# dc26-dev-boardv3.net
KiCad netlist of a schematic drawn in EAGLE
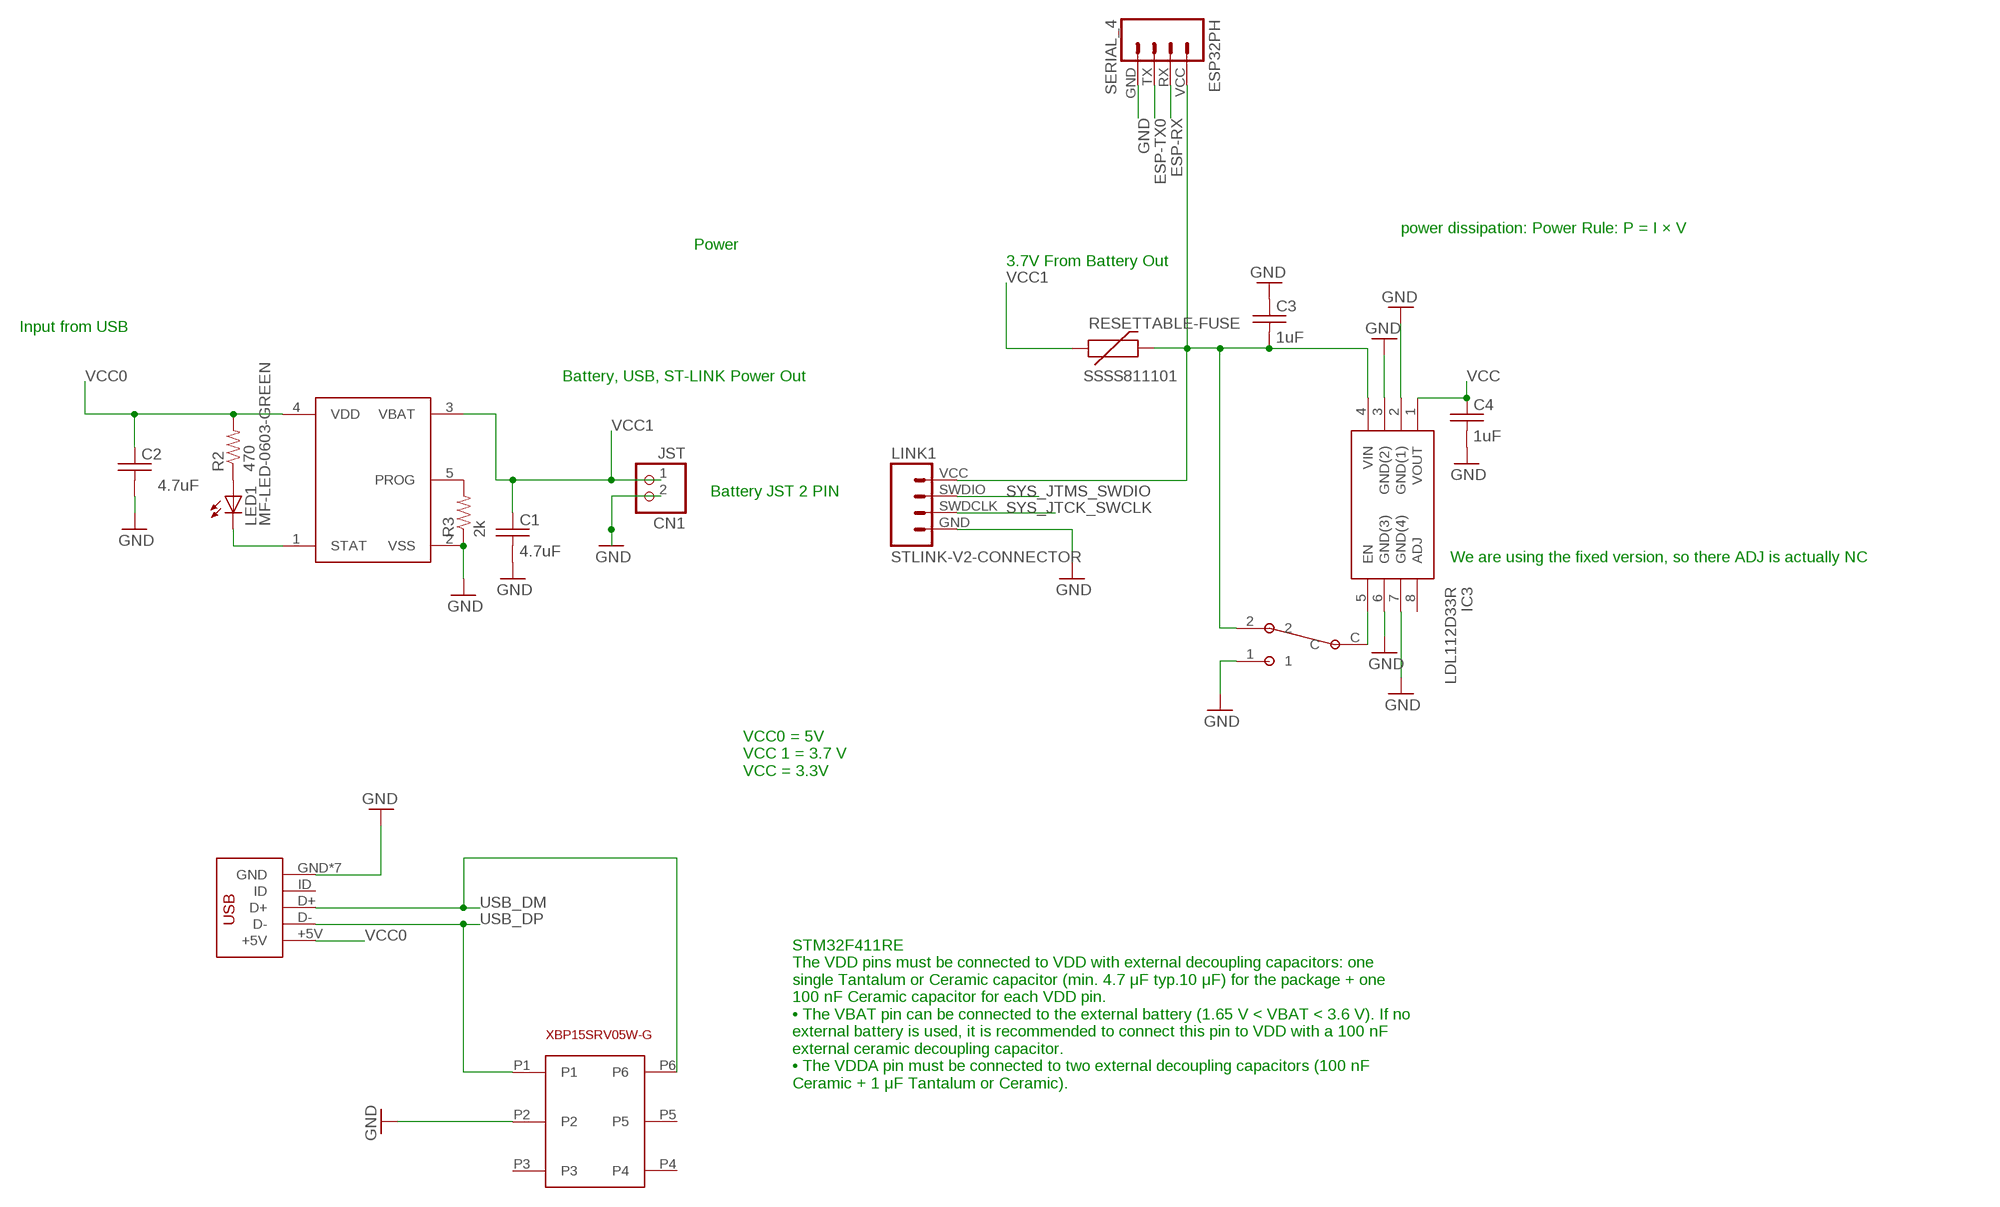
[diagram p0: schematic, sheet 1]
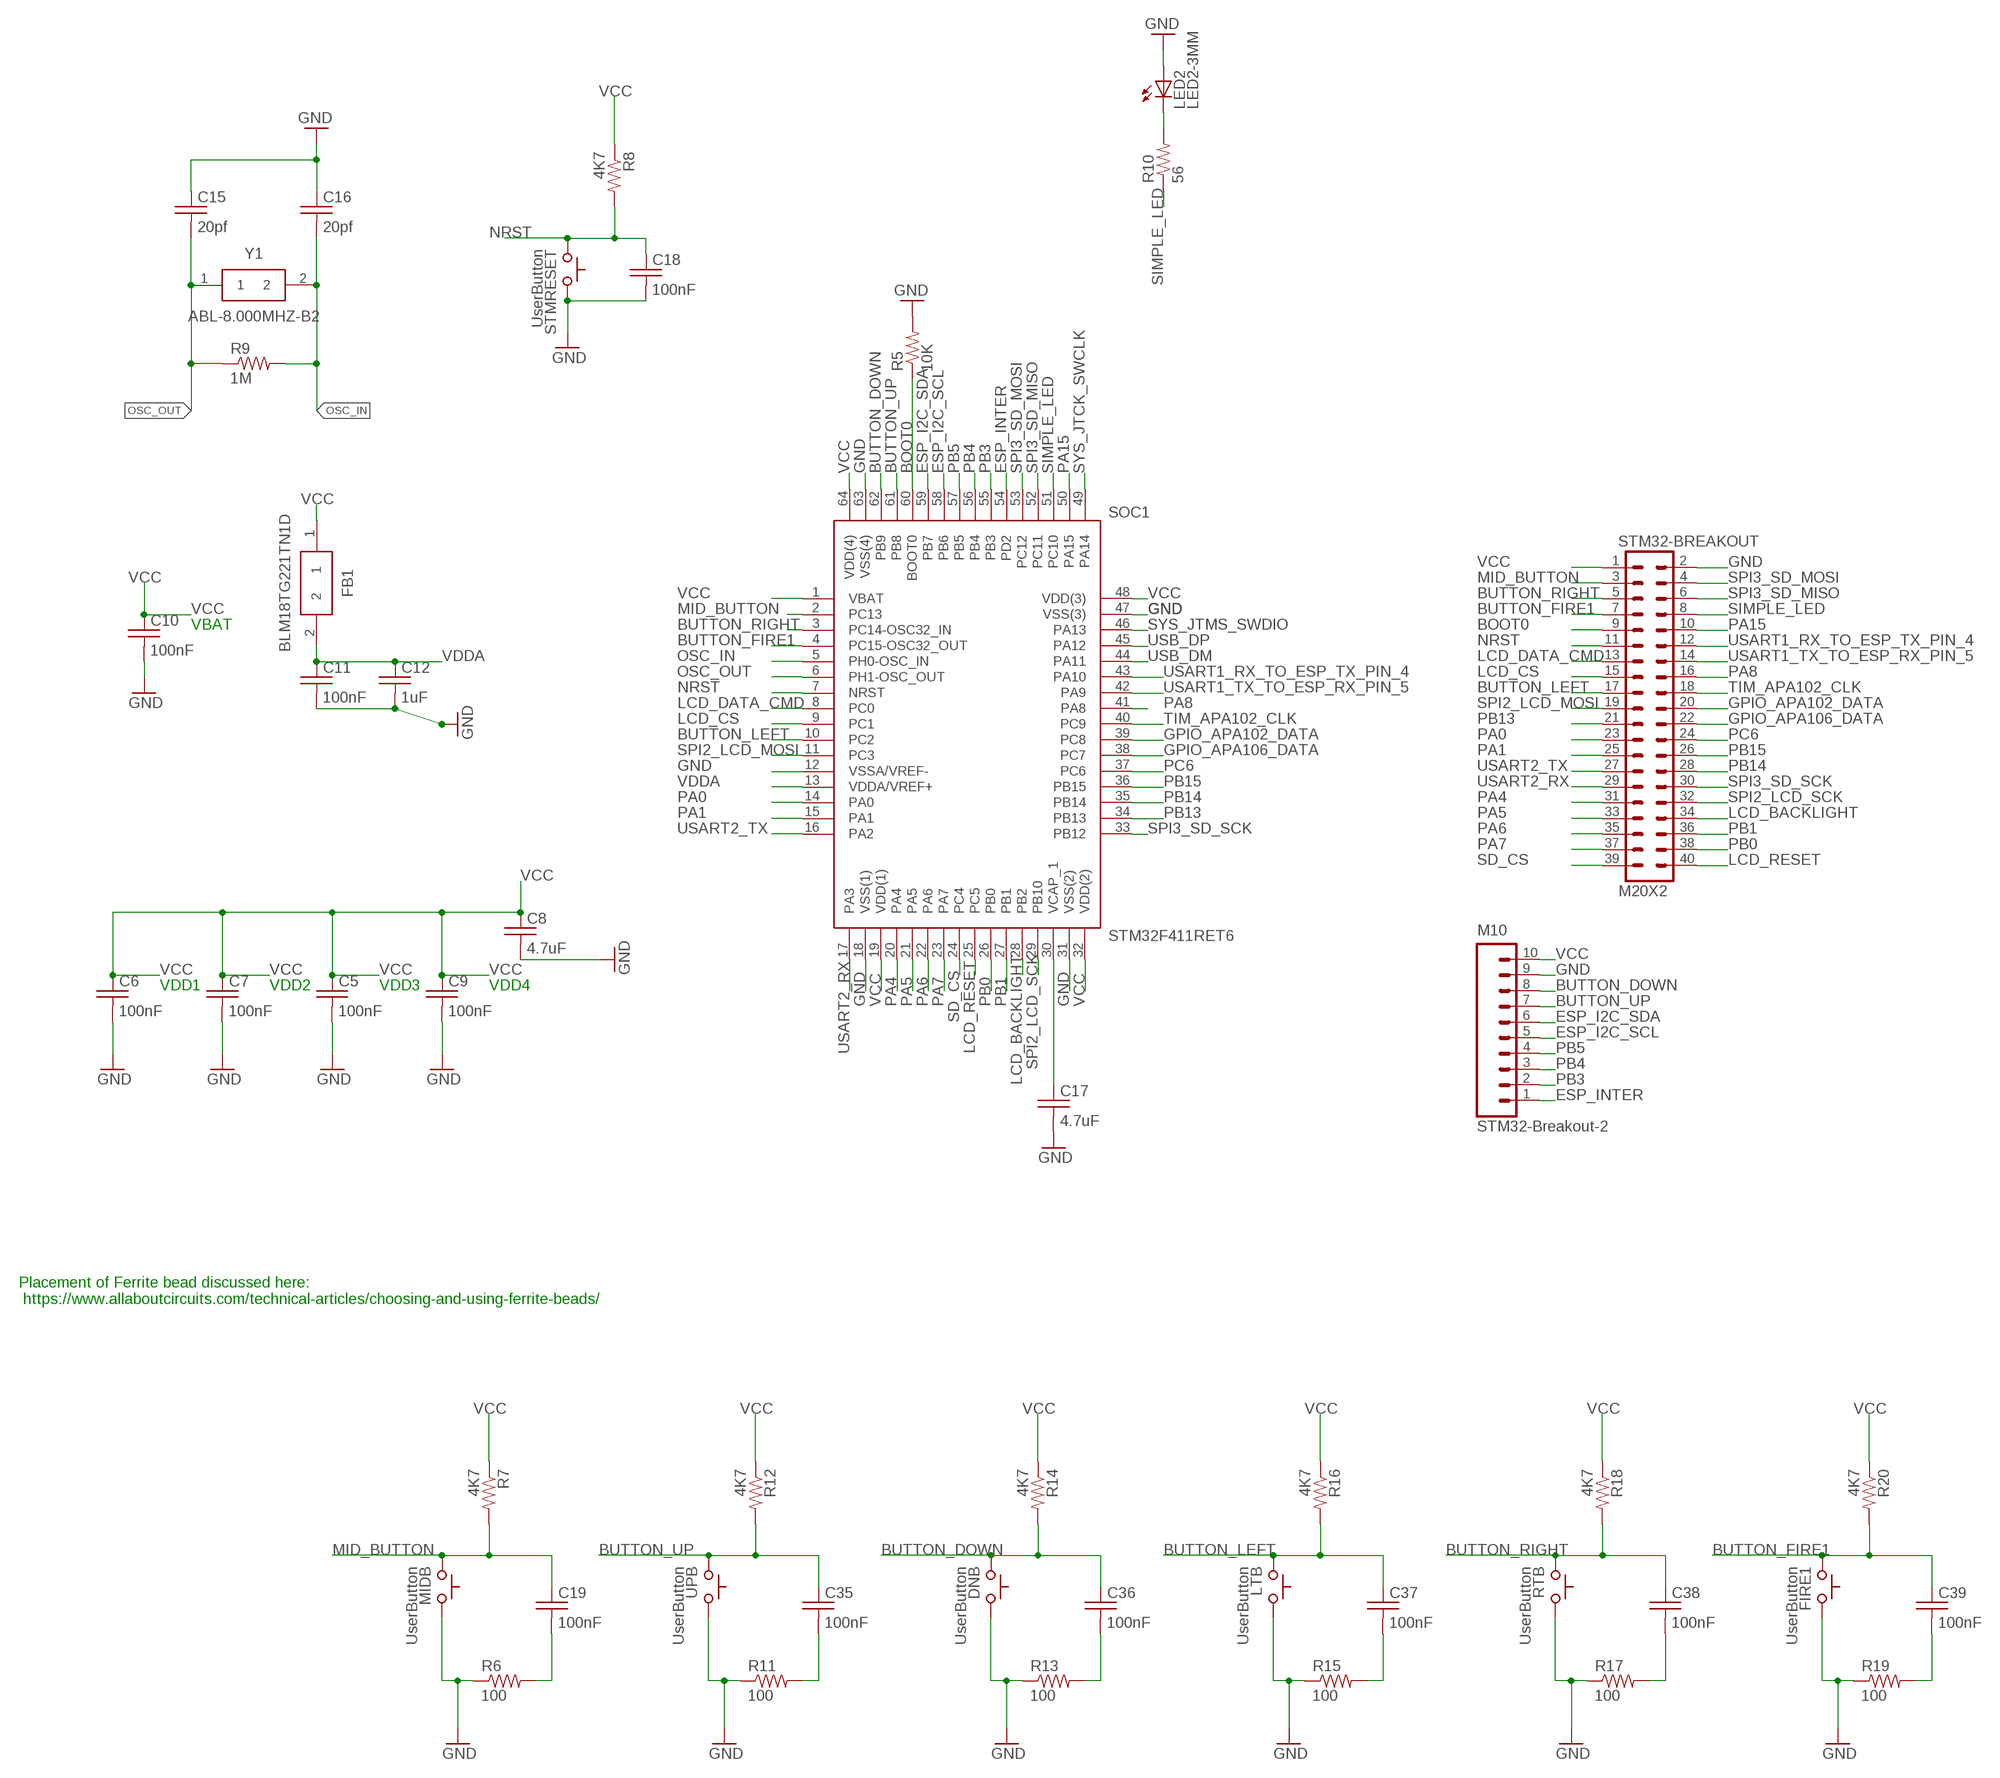
[diagram p1: schematic, sheet 2]
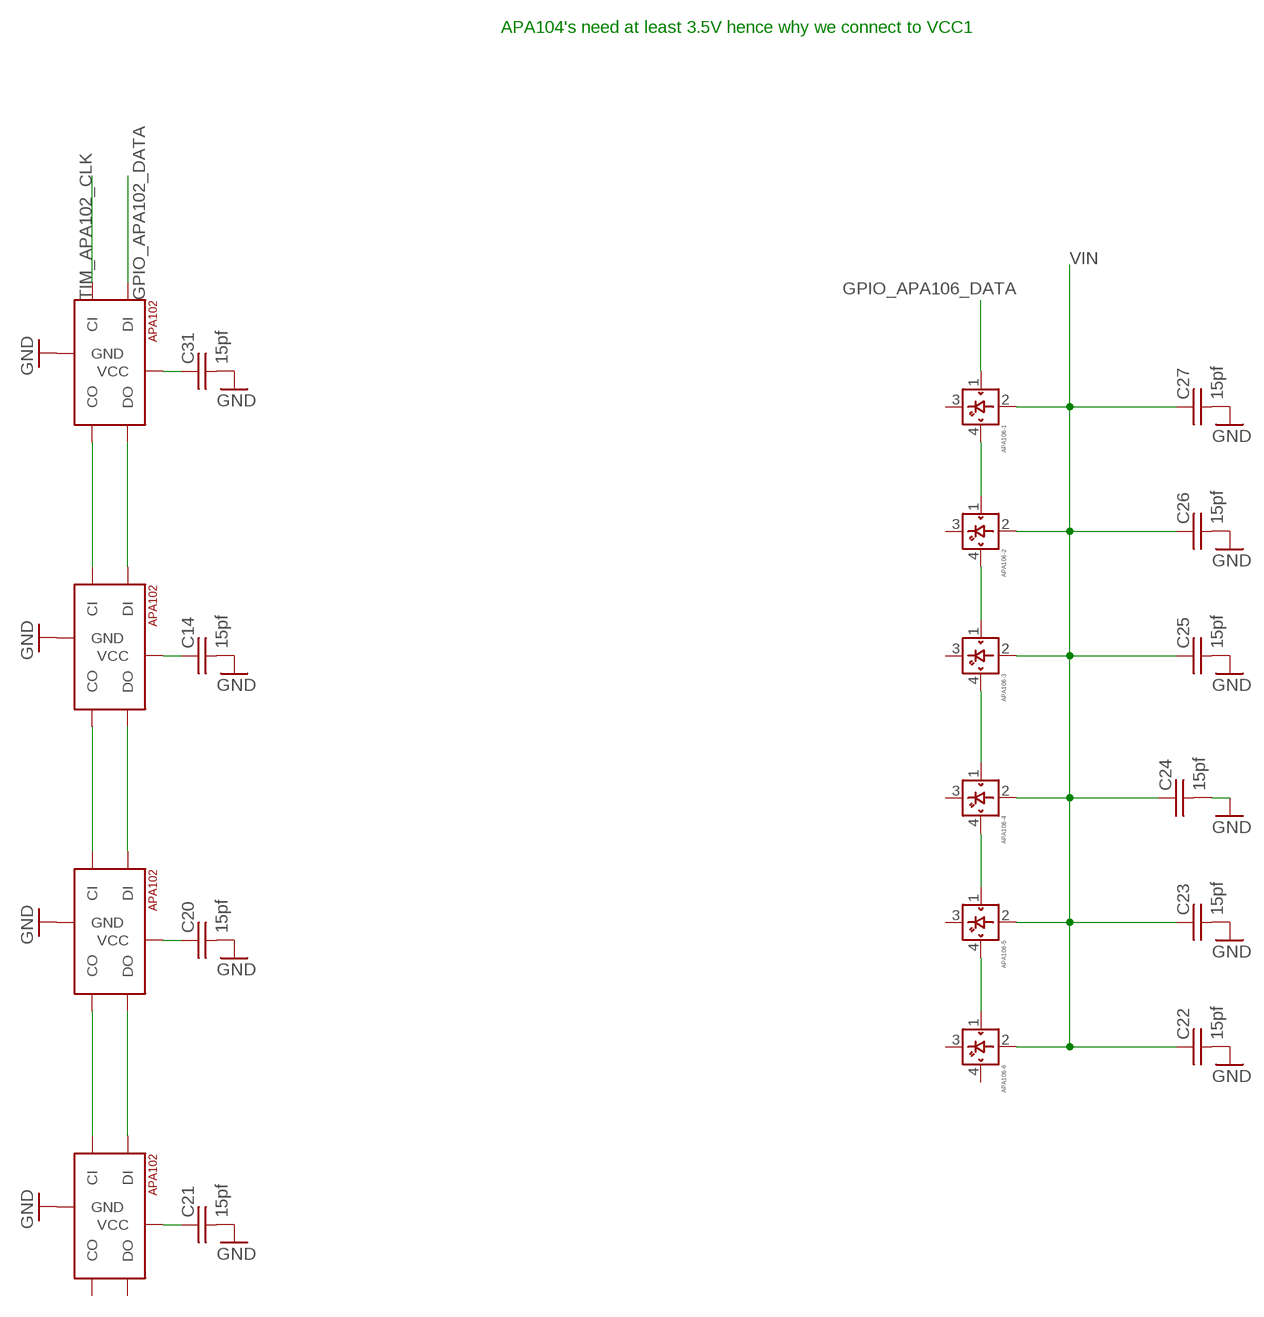
[diagram p2: schematic, sheet 3]
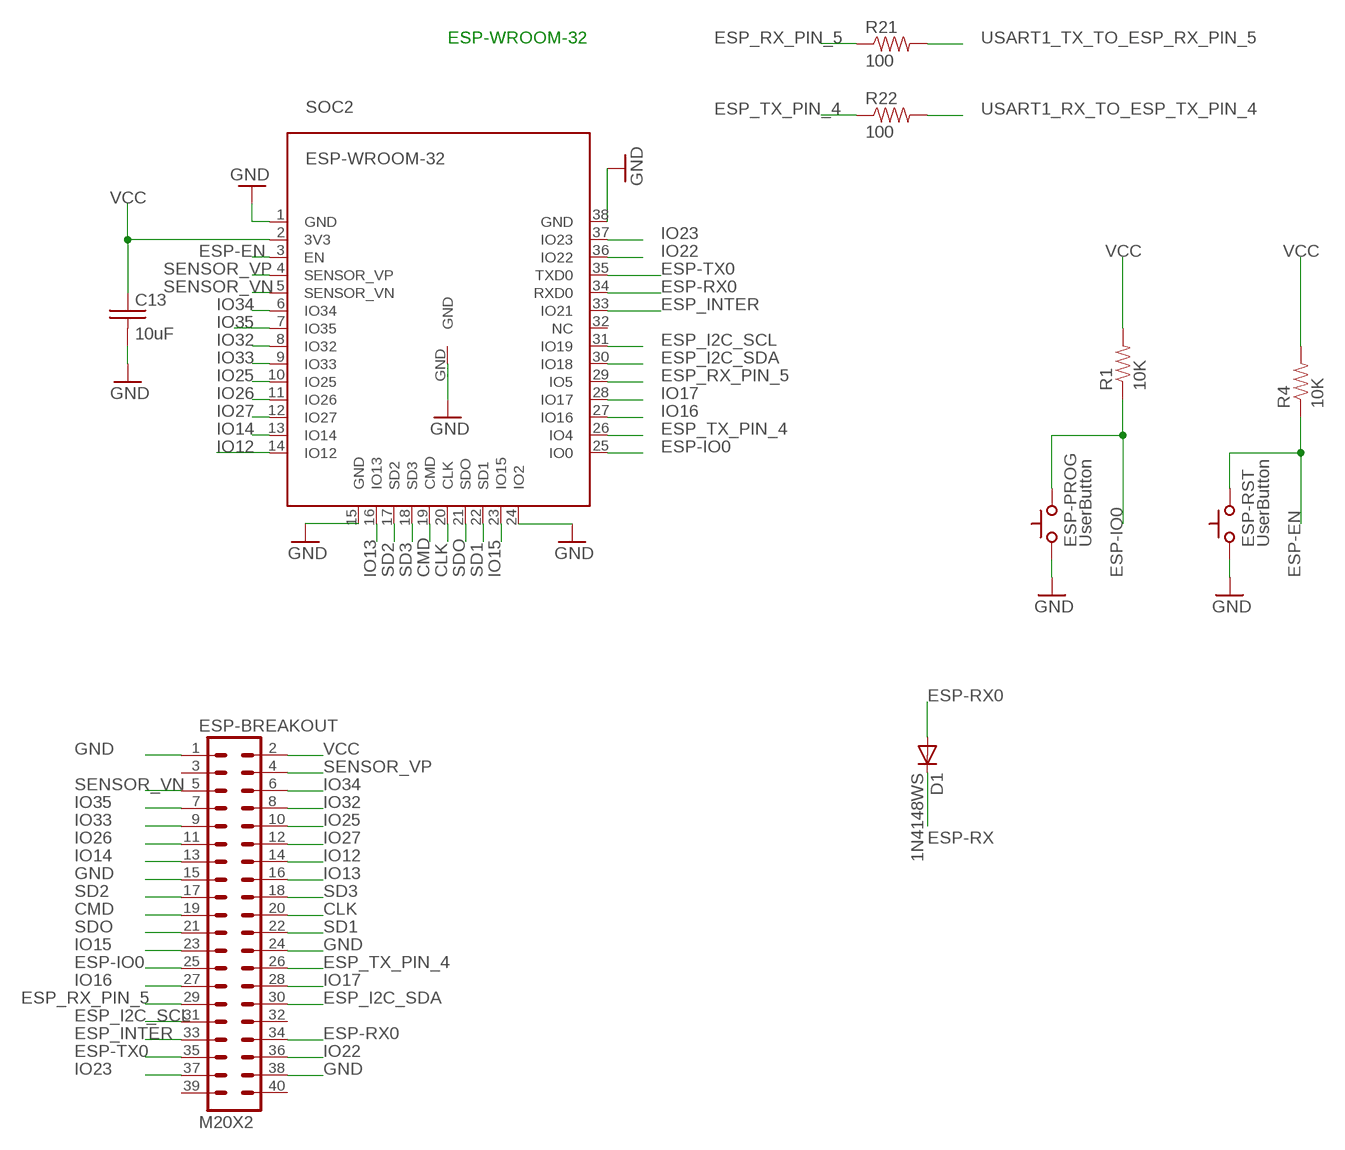
[diagram p3: schematic, sheet 4]
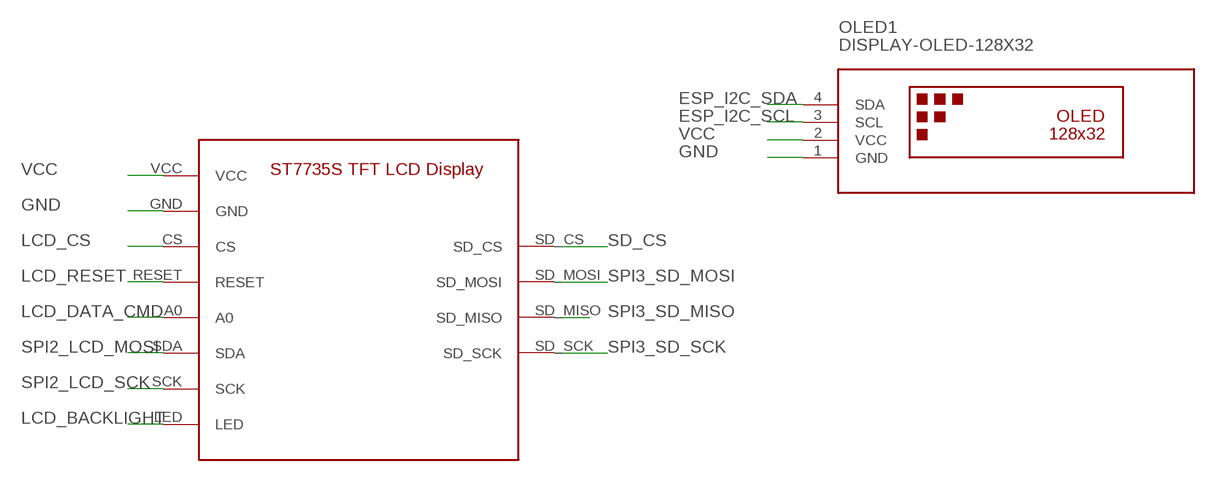
[diagram p4: schematic, sheet 5]
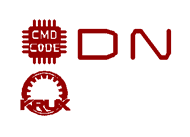
[diagram p5: schematic, sheet 6]
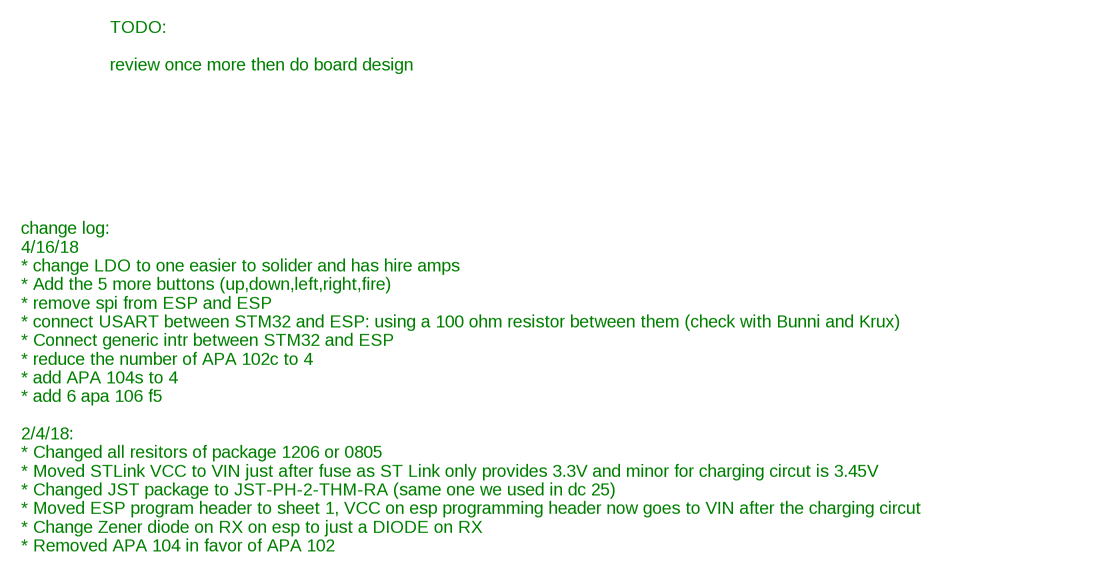
[diagram p6: schematic, sheet 7]

(export (version "E")
  (design (tool "Eeschema 10.0.6"))
  (components
    (comp (ref "C1")
      (value "4.7uF")
      (footprint "eagle-import:C0805")
      (libsource (lib "eagle-import") (part "C-USC0805"))
    )
    (comp (ref "C2")
      (value "4.7uF")
      (footprint "eagle-import:C0805")
      (libsource (lib "eagle-import") (part "C-USC0805"))
    )
    (comp (ref "C3")
      (value "1uF")
      (footprint "eagle-import:C0805")
      (libsource (lib "eagle-import") (part "C-USC0805"))
    )
    (comp (ref "C4")
      (value "1uF")
      (footprint "eagle-import:C0805")
      (libsource (lib "eagle-import") (part "C-USC0805"))
    )
    (comp (ref "CHARGING_CIRCUT")
      (value "MCP73831")
      (footprint "eagle-import:SOT23-5")
      (libsource (lib "eagle-import") (part "DS21984E"))
    )
    (comp (ref "CN1")
      (value "JST")
      (footprint "eagle-import:JST-PH-2-THM-RA")
      (libsource (lib "eagle-import") (part "JST_2PIN-THM-RA"))
    )
    (comp (ref "ESP32PH")
      (value "SERIAL_4")
      (footprint "eagle-import:SERIAL_HEADER_4")
      (libsource (lib "eagle-import") (part "SERIAL_4"))
    )
    (comp (ref "IC3")
      (value "LDL112D33R")
      (footprint "eagle-import:SOIC127P600X175-8N")
      (libsource (lib "eagle-import") (part "LDL112D33R"))
    )
    (comp (ref "LED1")
      (value "MF-LED-0603-GREEN")
      (footprint "eagle-import:LED-1206")
      (libsource (lib "eagle-import") (part "LED1206"))
    )
    (comp (ref "LINK1")
      (value "STLINK-V2-CONNECTOR")
      (footprint "eagle-import:1X04")
      (libsource (lib "eagle-import") (part "STLINK-V2-CONNECTOR"))
    )
    (comp (ref "P1")
      (value "SSSS811101")
      (footprint "eagle-import:SPDT_SSAJ120100")
      (libsource (lib "eagle-import") (part "SWITCH_SPDT"))
    )
    (comp (ref "R2")
      (value "470")
      (footprint "eagle-import:0805")
      (libsource (lib "eagle-import") (part "RESISTOR0805-RES"))
    )
    (comp (ref "R3")
      (value "2k")
      (footprint "eagle-import:0805")
      (libsource (lib "eagle-import") (part "RESISTOR0805-RES"))
    )
    (comp (ref "RESETTABLE-FUSE")
      (value "SSSS811101")
      (footprint "eagle-import:PTC-1206")
      (libsource (lib "eagle-import") (part "PTCSMD"))
    )
    (comp (ref "U$17")
      (value "XBP15SRV05W-G")
      (footprint "eagle-import:SOT-26P-XBP15SRV05W-G")
      (fields (field (name "DIGI_KEY_PART_NUMBER") "893-1422-1-ND"))
      (libsource (lib "eagle-import") (part "XBP15SRV05W-G"))
    )
    (comp (ref "USB")
      (value "DX4R005JJ2DX4R005JJ2")
      (footprint "eagle-import:DX4R005JJ2")
      (libsource (lib "eagle-import") (part "DX4R005JJ2DX4R005JJ2"))
    )
    (comp (ref "LCD1")
      (value "ST7735S_LCD_MODULE")
      (footprint "eagle-import:ST7735S_LCD_DISPLAY")
      (libsource (lib "eagle-import") (part "ST7735S_LCD_MODULE"))
    )
    (comp (ref "OLED1")
      (value "DISPLAY-OLED-128X32")
      (footprint "eagle-import:DISPLAY-OLED-128X32")
      (libsource (lib "eagle-import") (part "DISPLAY-OLED-128X32"))
    )
    (comp (ref "C13")
      (value "10uF")
      (footprint "eagle-import:C0805")
      (libsource (lib "eagle-import") (part "C-USC0805"))
    )
    (comp (ref "D1")
      (value "1N4148WS")
      (footprint "eagle-import:SOD-323")
      (libsource (lib "eagle-import") (part "DIODESOD"))
    )
    (comp (ref "ESP-BREAKOUT")
      (value "M20X2")
      (footprint "eagle-import:2X20")
      (libsource (lib "eagle-import") (part "M20X2"))
    )
    (comp (ref "ESP-PROG")
      (value "UserButton")
      (footprint "eagle-import:TACTILE-2PIN-NARROW")
      (libsource (lib "eagle-import") (part "SWITCH_TACTILETACTILE-2PIN-NARROW"))
    )
    (comp (ref "ESP-RST")
      (value "UserButton")
      (footprint "eagle-import:TACTILE-2PIN-NARROW")
      (libsource (lib "eagle-import") (part "SWITCH_TACTILETACTILE-2PIN-NARROW"))
    )
    (comp (ref "R1")
      (value "10K")
      (footprint "eagle-import:0805")
      (libsource (lib "eagle-import") (part "RESISTOR0805-RES"))
    )
    (comp (ref "R4")
      (value "10K")
      (footprint "eagle-import:0805")
      (libsource (lib "eagle-import") (part "RESISTOR0805-RES"))
    )
    (comp (ref "R21")
      (value "100")
      (footprint "eagle-import:0805")
      (libsource (lib "eagle-import") (part "RESISTOR0805-RES"))
    )
    (comp (ref "R22")
      (value "100")
      (footprint "eagle-import:0805")
      (libsource (lib "eagle-import") (part "RESISTOR0805-RES"))
    )
    (comp (ref "SOC2")
      (value "ESP-WROOM-32")
      (footprint "eagle-import:ESP-WROOM-32")
      (libsource (lib "eagle-import") (part "ESP-WROOM-32"))
    )
    (comp (ref "APA102-1")
      (value "APA1025050")
      (footprint "eagle-import:APA102_5050")
      (libsource (lib "eagle-import") (part "APA1025050"))
    )
    (comp (ref "APA102-2")
      (value "APA1025050")
      (footprint "eagle-import:APA102_5050")
      (libsource (lib "eagle-import") (part "APA1025050"))
    )
    (comp (ref "APA102-3")
      (value "APA1025050")
      (footprint "eagle-import:APA102_5050")
      (libsource (lib "eagle-import") (part "APA1025050"))
    )
    (comp (ref "APA102-4")
      (value "APA1025050")
      (footprint "eagle-import:APA102_5050")
      (libsource (lib "eagle-import") (part "APA1025050"))
    )
    (comp (ref "APA106-1")
      (value "APA-106")
      (footprint "eagle-import:WS2812F5_STRAIGHT")
      (libsource (lib "eagle-import") (part "APA-106"))
    )
    (comp (ref "APA106-2")
      (value "APA-106")
      (footprint "eagle-import:WS2812F5_STRAIGHT")
      (libsource (lib "eagle-import") (part "APA-106"))
    )
    (comp (ref "APA106-3")
      (value "APA-106")
      (footprint "eagle-import:WS2812F5_STRAIGHT")
      (libsource (lib "eagle-import") (part "APA-106"))
    )
    (comp (ref "APA106-4")
      (value "APA-106")
      (footprint "eagle-import:WS2812F5_STRAIGHT")
      (libsource (lib "eagle-import") (part "APA-106"))
    )
    (comp (ref "APA106-5")
      (value "APA-106")
      (footprint "eagle-import:WS2812F5_STRAIGHT")
      (libsource (lib "eagle-import") (part "APA-106"))
    )
    (comp (ref "APA106-6")
      (value "APA-106")
      (footprint "eagle-import:WS2812F5_STRAIGHT")
      (libsource (lib "eagle-import") (part "APA-106"))
    )
    (comp (ref "C14")
      (value "15pf")
      (footprint "eagle-import:C0805")
      (libsource (lib "eagle-import") (part "C-USC0805"))
    )
    (comp (ref "C20")
      (value "15pf")
      (footprint "eagle-import:C0805")
      (libsource (lib "eagle-import") (part "C-USC0805"))
    )
    (comp (ref "C21")
      (value "15pf")
      (footprint "eagle-import:C0805")
      (libsource (lib "eagle-import") (part "C-USC0805"))
    )
    (comp (ref "C22")
      (value "15pf")
      (footprint "eagle-import:C0805")
      (libsource (lib "eagle-import") (part "C-USC0805"))
    )
    (comp (ref "C23")
      (value "15pf")
      (footprint "eagle-import:C0805")
      (libsource (lib "eagle-import") (part "C-USC0805"))
    )
    (comp (ref "C24")
      (value "15pf")
      (footprint "eagle-import:C0805")
      (libsource (lib "eagle-import") (part "C-USC0805"))
    )
    (comp (ref "C25")
      (value "15pf")
      (footprint "eagle-import:C0805")
      (libsource (lib "eagle-import") (part "C-USC0805"))
    )
    (comp (ref "C26")
      (value "15pf")
      (footprint "eagle-import:C0805")
      (libsource (lib "eagle-import") (part "C-USC0805"))
    )
    (comp (ref "C27")
      (value "15pf")
      (footprint "eagle-import:C0805")
      (libsource (lib "eagle-import") (part "C-USC0805"))
    )
    (comp (ref "C31")
      (value "15pf")
      (footprint "eagle-import:C0805")
      (libsource (lib "eagle-import") (part "C-USC0805"))
    )
    (comp (ref "U$2")
      (value "CMD_C0DE_LOGO")
      (footprint "eagle-import:CMD_C0DE_LOGO")
      (libsource (lib "eagle-import") (part "CMD_C0DE_LOGO"))
    )
    (comp (ref "U$3")
      (value "DARKNET_DD")
      (footprint "eagle-import:DARKNET_D")
      (libsource (lib "eagle-import") (part "DARKNET_DD"))
    )
    (comp (ref "U$4")
      (value "DARKNET_NN")
      (footprint "eagle-import:DARKNET_N")
      (libsource (lib "eagle-import") (part "DARKNET_NN"))
    )
    (comp (ref "U$16")
      (value "KRUX_LOGO")
      (footprint "eagle-import:KRUX_LOGO")
      (libsource (lib "eagle-import") (part "KRUX_LOGO"))
    )
    (comp (ref "C5")
      (value "100nF")
      (footprint "eagle-import:C0805")
      (libsource (lib "eagle-import") (part "C-USC0805"))
    )
    (comp (ref "C6")
      (value "100nF")
      (footprint "eagle-import:C0805")
      (libsource (lib "eagle-import") (part "C-USC0805"))
    )
    (comp (ref "C7")
      (value "100nF")
      (footprint "eagle-import:C0805")
      (libsource (lib "eagle-import") (part "C-USC0805"))
    )
    (comp (ref "C8")
      (value "4.7uF")
      (footprint "eagle-import:C0805")
      (libsource (lib "eagle-import") (part "C-USC0805"))
    )
    (comp (ref "C9")
      (value "100nF")
      (footprint "eagle-import:C0805")
      (libsource (lib "eagle-import") (part "C-USC0805"))
    )
    (comp (ref "C10")
      (value "100nF")
      (footprint "eagle-import:C0805")
      (libsource (lib "eagle-import") (part "C-USC0805"))
    )
    (comp (ref "C11")
      (value "100nF")
      (footprint "eagle-import:C0805")
      (libsource (lib "eagle-import") (part "C-USC0805"))
    )
    (comp (ref "C12")
      (value "1uF")
      (footprint "eagle-import:C0805")
      (libsource (lib "eagle-import") (part "C-USC0805"))
    )
    (comp (ref "C15")
      (value "20pf")
      (footprint "eagle-import:C0805")
      (libsource (lib "eagle-import") (part "C-USC0805"))
    )
    (comp (ref "C16")
      (value "20pf")
      (footprint "eagle-import:C0805")
      (libsource (lib "eagle-import") (part "C-USC0805"))
    )
    (comp (ref "C17")
      (value "4.7uF")
      (footprint "eagle-import:C0805")
      (libsource (lib "eagle-import") (part "C-USC0805"))
    )
    (comp (ref "C18")
      (value "100nF")
      (footprint "eagle-import:C0805")
      (libsource (lib "eagle-import") (part "C-USC0805"))
    )
    (comp (ref "C19")
      (value "100nF")
      (footprint "eagle-import:C0805")
      (libsource (lib "eagle-import") (part "C-USC0805"))
    )
    (comp (ref "C35")
      (value "100nF")
      (footprint "eagle-import:C0805")
      (libsource (lib "eagle-import") (part "C-USC0805"))
    )
    (comp (ref "C36")
      (value "100nF")
      (footprint "eagle-import:C0805")
      (libsource (lib "eagle-import") (part "C-USC0805"))
    )
    (comp (ref "C37")
      (value "100nF")
      (footprint "eagle-import:C0805")
      (libsource (lib "eagle-import") (part "C-USC0805"))
    )
    (comp (ref "C38")
      (value "100nF")
      (footprint "eagle-import:C0805")
      (libsource (lib "eagle-import") (part "C-USC0805"))
    )
    (comp (ref "C39")
      (value "100nF")
      (footprint "eagle-import:C0805")
      (libsource (lib "eagle-import") (part "C-USC0805"))
    )
    (comp (ref "DNB")
      (value "UserButton")
      (footprint "eagle-import:TACTILE-2PIN-NARROW")
      (libsource (lib "eagle-import") (part "SWITCH_TACTILETACTILE-2PIN-NARROW"))
    )
    (comp (ref "FB1")
      (value "BLM18TG221TN1D")
      (footprint "eagle-import:BEADC1608X75N")
      (fields (field (name "RS_PART_NUMBER") "6197526"))
      (libsource (lib "eagle-import") (part "BLM18TG221TN1D"))
    )
    (comp (ref "FIRE1")
      (value "UserButton")
      (footprint "eagle-import:TACTILE-2PIN-NARROW")
      (libsource (lib "eagle-import") (part "SWITCH_TACTILETACTILE-2PIN-NARROW"))
    )
    (comp (ref "LED2")
      (value "LED2-3MM")
      (footprint "eagle-import:LED3MM")
      (libsource (lib "eagle-import") (part "LED3MM"))
    )
    (comp (ref "LTB")
      (value "UserButton")
      (footprint "eagle-import:TACTILE-2PIN-NARROW")
      (libsource (lib "eagle-import") (part "SWITCH_TACTILETACTILE-2PIN-NARROW"))
    )
    (comp (ref "M10")
      (value "STM32-Breakout-2")
      (footprint "eagle-import:1X10")
      (libsource (lib "eagle-import") (part "M10SILK_FEMALE_PTH"))
    )
    (comp (ref "MIDB")
      (value "UserButton")
      (footprint "eagle-import:TACTILE-2PIN-NARROW")
      (libsource (lib "eagle-import") (part "SWITCH_TACTILETACTILE-2PIN-NARROW"))
    )
    (comp (ref "R5")
      (value "10K")
      (footprint "eagle-import:0805")
      (libsource (lib "eagle-import") (part "RESISTOR0805-RES"))
    )
    (comp (ref "R6")
      (value "100")
      (footprint "eagle-import:0805")
      (libsource (lib "eagle-import") (part "RESISTOR0805-RES"))
    )
    (comp (ref "R7")
      (value "4K7")
      (footprint "eagle-import:0805")
      (libsource (lib "eagle-import") (part "RESISTOR0805-RES"))
    )
    (comp (ref "R8")
      (value "4K7")
      (footprint "eagle-import:0805")
      (libsource (lib "eagle-import") (part "RESISTOR0805-RES"))
    )
    (comp (ref "R9")
      (value "1M")
      (footprint "eagle-import:0805")
      (libsource (lib "eagle-import") (part "RESISTOR0805-RES"))
    )
    (comp (ref "R10")
      (value "56")
      (footprint "eagle-import:0805")
      (libsource (lib "eagle-import") (part "RESISTOR0805-RES"))
    )
    (comp (ref "R11")
      (value "100")
      (footprint "eagle-import:0805")
      (libsource (lib "eagle-import") (part "RESISTOR0805-RES"))
    )
    (comp (ref "R12")
      (value "4K7")
      (footprint "eagle-import:0805")
      (libsource (lib "eagle-import") (part "RESISTOR0805-RES"))
    )
    (comp (ref "R13")
      (value "100")
      (footprint "eagle-import:0805")
      (libsource (lib "eagle-import") (part "RESISTOR0805-RES"))
    )
    (comp (ref "R14")
      (value "4K7")
      (footprint "eagle-import:0805")
      (libsource (lib "eagle-import") (part "RESISTOR0805-RES"))
    )
    (comp (ref "R15")
      (value "100")
      (footprint "eagle-import:0805")
      (libsource (lib "eagle-import") (part "RESISTOR0805-RES"))
    )
    (comp (ref "R16")
      (value "4K7")
      (footprint "eagle-import:0805")
      (libsource (lib "eagle-import") (part "RESISTOR0805-RES"))
    )
    (comp (ref "R17")
      (value "100")
      (footprint "eagle-import:0805")
      (libsource (lib "eagle-import") (part "RESISTOR0805-RES"))
    )
    (comp (ref "R18")
      (value "4K7")
      (footprint "eagle-import:0805")
      (libsource (lib "eagle-import") (part "RESISTOR0805-RES"))
    )
    (comp (ref "R19")
      (value "100")
      (footprint "eagle-import:0805")
      (libsource (lib "eagle-import") (part "RESISTOR0805-RES"))
    )
    (comp (ref "R20")
      (value "4K7")
      (footprint "eagle-import:0805")
      (libsource (lib "eagle-import") (part "RESISTOR0805-RES"))
    )
    (comp (ref "RTB")
      (value "UserButton")
      (footprint "eagle-import:TACTILE-2PIN-NARROW")
      (libsource (lib "eagle-import") (part "SWITCH_TACTILETACTILE-2PIN-NARROW"))
    )
    (comp (ref "SOC1")
      (value "STM32F411RET6")
      (footprint "eagle-import:QFP50P1200X1200X160-64N")
      (fields (field (name "RS_PART_NUMBER") "1106617P"))
      (libsource (lib "eagle-import") (part "STM32F411RET6"))
    )
    (comp (ref "STM32-BREAKOUT")
      (value "M20X2")
      (footprint "eagle-import:2X20")
      (libsource (lib "eagle-import") (part "M20X2"))
    )
    (comp (ref "STMRESET")
      (value "UserButton")
      (footprint "eagle-import:TACTILE-2PIN-NARROW")
      (libsource (lib "eagle-import") (part "SWITCH_TACTILETACTILE-2PIN-NARROW"))
    )
    (comp (ref "UPB")
      (value "UserButton")
      (footprint "eagle-import:TACTILE-2PIN-NARROW")
      (libsource (lib "eagle-import") (part "SWITCH_TACTILETACTILE-2PIN-NARROW"))
    )
    (comp (ref "Y1")
      (value "ABL-8.000MHZ-B2")
      (footprint "eagle-import:HC_49US_(AT49)PTH")
      (libsource (lib "eagle-import") (part "ABL-8.000MHZ-B2"))
    )
  )
  (nets
    (net (code "1") (name "BOOT0") (class "Default")
      (node (ref "R5") (pin "1") (pinfunction "1_1") (pintype "passive"))
      (node (ref "SOC1") (pin "60") (pinfunction "BOOT0_60") (pintype "passive"))
      (node (ref "STM32-BREAKOUT") (pin "9") (pinfunction "9_9") (pintype "passive"))
    )
    (net (code "2") (name "BUTTON_DOWN") (class "Default")
      (node (ref "C36") (pin "1") (pinfunction "1_1") (pintype "passive"))
      (node (ref "DNB") (pin "P$2") (pinfunction "C_P$2") (pintype "passive"))
      (node (ref "M10") (pin "8") (pinfunction "8_8") (pintype "passive"))
      (node (ref "R14") (pin "2") (pinfunction "2_2") (pintype "passive"))
      (node (ref "SOC1") (pin "62") (pinfunction "PB9_62") (pintype "passive"))
    )
    (net (code "3") (name "BUTTON_FIRE1") (class "Default")
      (node (ref "C39") (pin "1") (pinfunction "1_1") (pintype "passive"))
      (node (ref "FIRE1") (pin "P$2") (pinfunction "C_P$2") (pintype "passive"))
      (node (ref "R20") (pin "2") (pinfunction "2_2") (pintype "passive"))
      (node (ref "SOC1") (pin "4") (pinfunction "PC15-OSC32_OUT_4") (pintype "passive"))
      (node (ref "STM32-BREAKOUT") (pin "7") (pinfunction "7_7") (pintype "passive"))
    )
    (net (code "4") (name "BUTTON_LEFT") (class "Default")
      (node (ref "C37") (pin "1") (pinfunction "1_1") (pintype "passive"))
      (node (ref "LTB") (pin "P$2") (pinfunction "C_P$2") (pintype "passive"))
      (node (ref "R16") (pin "2") (pinfunction "2_2") (pintype "passive"))
      (node (ref "SOC1") (pin "10") (pinfunction "PC2_10") (pintype "passive"))
      (node (ref "STM32-BREAKOUT") (pin "17") (pinfunction "17_17") (pintype "passive"))
    )
    (net (code "5") (name "BUTTON_RIGHT") (class "Default")
      (node (ref "C38") (pin "1") (pinfunction "1_1") (pintype "passive"))
      (node (ref "R18") (pin "2") (pinfunction "2_2") (pintype "passive"))
      (node (ref "RTB") (pin "P$2") (pinfunction "C_P$2") (pintype "passive"))
      (node (ref "SOC1") (pin "3") (pinfunction "PC14-OSC32_IN_3") (pintype "passive"))
      (node (ref "STM32-BREAKOUT") (pin "5") (pinfunction "5_5") (pintype "passive"))
    )
    (net (code "6") (name "BUTTON_UP") (class "Default")
      (node (ref "C35") (pin "1") (pinfunction "1_1") (pintype "passive"))
      (node (ref "M10") (pin "7") (pinfunction "7_7") (pintype "passive"))
      (node (ref "R12") (pin "2") (pinfunction "2_2") (pintype "passive"))
      (node (ref "SOC1") (pin "61") (pinfunction "PB8_61") (pintype "passive"))
      (node (ref "UPB") (pin "P$2") (pinfunction "C_P$2") (pintype "passive"))
    )
    (net (code "7") (name "CLK") (class "Default")
      (node (ref "ESP-BREAKOUT") (pin "20") (pinfunction "20_20") (pintype "passive"))
      (node (ref "SOC2") (pin "20") (pinfunction "CLK_20") (pintype "bidirectional"))
    )
    (net (code "8") (name "CMD") (class "Default")
      (node (ref "ESP-BREAKOUT") (pin "19") (pinfunction "19_19") (pintype "passive"))
      (node (ref "SOC2") (pin "19") (pinfunction "CMD_19") (pintype "bidirectional"))
    )
    (net (code "9") (name "ESP-EN") (class "Default")
      (node (ref "ESP-RST") (pin "P$1") (pinfunction "A_P$1") (pintype "passive"))
      (node (ref "R4") (pin "1") (pinfunction "1_1") (pintype "passive"))
      (node (ref "SOC2") (pin "3") (pinfunction "EN_3") (pintype "bidirectional"))
    )
    (net (code "10") (name "ESP-IO0") (class "Default")
      (node (ref "ESP-BREAKOUT") (pin "25") (pinfunction "25_25") (pintype "passive"))
      (node (ref "ESP-PROG") (pin "P$1") (pinfunction "A_P$1") (pintype "passive"))
      (node (ref "R1") (pin "1") (pinfunction "1_1") (pintype "passive"))
      (node (ref "SOC2") (pin "25") (pinfunction "IO0_25") (pintype "bidirectional"))
    )
    (net (code "11") (name "ESP-RX") (class "Default")
      (node (ref "D1") (pin "1") (pinfunction "C_1") (pintype "passive"))
      (node (ref "ESP32PH") (pin "RX") (pinfunction "RX_RX") (pintype "bidirectional"))
    )
    (net (code "12") (name "ESP-RX0") (class "Default")
      (node (ref "D1") (pin "2") (pinfunction "A_2") (pintype "passive"))
      (node (ref "ESP-BREAKOUT") (pin "34") (pinfunction "34_34") (pintype "passive"))
      (node (ref "SOC2") (pin "34") (pinfunction "RXD0_34") (pintype "bidirectional"))
    )
    (net (code "13") (name "ESP-TX0") (class "Default")
      (node (ref "ESP-BREAKOUT") (pin "35") (pinfunction "35_35") (pintype "passive"))
      (node (ref "ESP32PH") (pin "TX") (pinfunction "TX_TX") (pintype "input"))
      (node (ref "SOC2") (pin "35") (pinfunction "TXD0_35") (pintype "bidirectional"))
    )
    (net (code "14") (name "ESP_I2C_SCL") (class "Default")
      (node (ref "ESP-BREAKOUT") (pin "31") (pinfunction "31_31") (pintype "passive"))
      (node (ref "M10") (pin "5") (pinfunction "5_5") (pintype "passive"))
      (node (ref "OLED1") (pin "3") (pinfunction "SCL_3") (pintype "bidirectional"))
      (node (ref "SOC1") (pin "58") (pinfunction "PB6_58") (pintype "passive"))
      (node (ref "SOC2") (pin "31") (pinfunction "IO19_31") (pintype "bidirectional"))
    )
    (net (code "15") (name "ESP_I2C_SDA") (class "Default")
      (node (ref "ESP-BREAKOUT") (pin "30") (pinfunction "30_30") (pintype "passive"))
      (node (ref "M10") (pin "6") (pinfunction "6_6") (pintype "passive"))
      (node (ref "OLED1") (pin "4") (pinfunction "SDA_4") (pintype "bidirectional"))
      (node (ref "SOC1") (pin "59") (pinfunction "PB7_59") (pintype "passive"))
      (node (ref "SOC2") (pin "30") (pinfunction "IO18_30") (pintype "bidirectional"))
    )
    (net (code "16") (name "ESP_INTER") (class "Default")
      (node (ref "ESP-BREAKOUT") (pin "33") (pinfunction "33_33") (pintype "passive"))
      (node (ref "M10") (pin "1") (pinfunction "1_1") (pintype "passive"))
      (node (ref "SOC1") (pin "54") (pinfunction "PD2_54") (pintype "passive"))
      (node (ref "SOC2") (pin "33") (pinfunction "IO21_33") (pintype "bidirectional"))
    )
    (net (code "17") (name "ESP_RX_PIN_5") (class "Default")
      (node (ref "ESP-BREAKOUT") (pin "29") (pinfunction "29_29") (pintype "passive"))
      (node (ref "R21") (pin "1") (pinfunction "1_1") (pintype "passive"))
      (node (ref "SOC2") (pin "29") (pinfunction "IO5_29") (pintype "bidirectional"))
    )
    (net (code "18") (name "ESP_TX_PIN_4") (class "Default")
      (node (ref "ESP-BREAKOUT") (pin "26") (pinfunction "26_26") (pintype "passive"))
      (node (ref "R22") (pin "1") (pinfunction "1_1") (pintype "passive"))
      (node (ref "SOC2") (pin "26") (pinfunction "IO4_26") (pintype "bidirectional"))
    )
    (net (code "19") (name "GND") (class "Default")
      (node (ref "APA102-1") (pin "6") (pinfunction "GND_6") (pintype "bidirectional"))
      (node (ref "APA102-2") (pin "6") (pinfunction "GND_6") (pintype "bidirectional"))
      (node (ref "APA102-3") (pin "6") (pinfunction "GND_6") (pintype "bidirectional"))
      (node (ref "APA102-4") (pin "6") (pinfunction "GND_6") (pintype "bidirectional"))
      (node (ref "C1") (pin "2") (pinfunction "2_2") (pintype "passive"))
      (node (ref "C10") (pin "2") (pinfunction "2_2") (pintype "passive"))
      (node (ref "C11") (pin "2") (pinfunction "2_2") (pintype "passive"))
      (node (ref "C12") (pin "2") (pinfunction "2_2") (pintype "passive"))
      (node (ref "C13") (pin "2") (pinfunction "2_2") (pintype "passive"))
      (node (ref "C14") (pin "2") (pinfunction "2_2") (pintype "passive"))
      (node (ref "C15") (pin "1") (pinfunction "1_1") (pintype "passive"))
      (node (ref "C16") (pin "1") (pinfunction "1_1") (pintype "passive"))
      (node (ref "C17") (pin "2") (pinfunction "2_2") (pintype "passive"))
      (node (ref "C18") (pin "2") (pinfunction "2_2") (pintype "passive"))
      (node (ref "C2") (pin "2") (pinfunction "2_2") (pintype "passive"))
      (node (ref "C20") (pin "2") (pinfunction "2_2") (pintype "passive"))
      (node (ref "C21") (pin "2") (pinfunction "2_2") (pintype "passive"))
      (node (ref "C22") (pin "2") (pinfunction "2_2") (pintype "passive"))
      (node (ref "C23") (pin "2") (pinfunction "2_2") (pintype "passive"))
      (node (ref "C24") (pin "2") (pinfunction "2_2") (pintype "passive"))
      (node (ref "C25") (pin "2") (pinfunction "2_2") (pintype "passive"))
      (node (ref "C26") (pin "2") (pinfunction "2_2") (pintype "passive"))
      (node (ref "C27") (pin "2") (pinfunction "2_2") (pintype "passive"))
      (node (ref "C3") (pin "1") (pinfunction "1_1") (pintype "passive"))
      (node (ref "C31") (pin "2") (pinfunction "2_2") (pintype "passive"))
      (node (ref "C4") (pin "2") (pinfunction "2_2") (pintype "passive"))
      (node (ref "C5") (pin "2") (pinfunction "2_2") (pintype "passive"))
      (node (ref "C6") (pin "2") (pinfunction "2_2") (pintype "passive"))
      (node (ref "C7") (pin "2") (pinfunction "2_2") (pintype "passive"))
      (node (ref "C8") (pin "2") (pinfunction "2_2") (pintype "passive"))
      (node (ref "C9") (pin "2") (pinfunction "2_2") (pintype "passive"))
      (node (ref "CHARGING_CIRCUT") (pin "2") (pinfunction "VSS_2") (pintype "bidirectional"))
      (node (ref "CN1") (pin "2") (pinfunction "1_2") (pintype "passive"))
      (node (ref "DNB") (pin "P$1") (pinfunction "A_P$1") (pintype "passive"))
      (node (ref "ESP-BREAKOUT") (pin "1") (pinfunction "1_1") (pintype "passive"))
      (node (ref "ESP-BREAKOUT") (pin "15") (pinfunction "15_15") (pintype "passive"))
      (node (ref "ESP-BREAKOUT") (pin "24") (pinfunction "24_24") (pintype "passive"))
      (node (ref "ESP-BREAKOUT") (pin "38") (pinfunction "38_38") (pintype "passive"))
      (node (ref "ESP-PROG") (pin "P$2") (pinfunction "C_P$2") (pintype "passive"))
      (node (ref "ESP-RST") (pin "P$2") (pinfunction "C_P$2") (pintype "passive"))
      (node (ref "ESP32PH") (pin "GND") (pinfunction "GND_GND") (pintype "power_in"))
      (node (ref "FIRE1") (pin "P$1") (pinfunction "A_P$1") (pintype "passive"))
      (node (ref "IC3") (pin "2") (pinfunction "GND(1)_2") (pintype "bidirectional"))
      (node (ref "IC3") (pin "3") (pinfunction "GND(2)_3") (pintype "bidirectional"))
      (node (ref "IC3") (pin "6") (pinfunction "GND(3)_6") (pintype "bidirectional"))
      (node (ref "IC3") (pin "7") (pinfunction "GND(4)_7") (pintype "bidirectional"))
      (node (ref "LCD1") (pin "GND") (pinfunction "GND_GND") (pintype "bidirectional"))
      (node (ref "LED2") (pin "A") (pinfunction "A_A") (pintype "input"))
      (node (ref "LINK1") (pin "GND") (pinfunction "GND_GND") (pintype "power_in"))
      (node (ref "LTB") (pin "P$1") (pinfunction "A_P$1") (pintype "passive"))
      (node (ref "M10") (pin "9") (pinfunction "9_9") (pintype "passive"))
      (node (ref "MIDB") (pin "P$1") (pinfunction "A_P$1") (pintype "passive"))
      (node (ref "OLED1") (pin "1") (pinfunction "GND_1") (pintype "power_in"))
      (node (ref "P1") (pin "1") (pinfunction "1_1") (pintype "bidirectional"))
      (node (ref "R11") (pin "1") (pinfunction "1_1") (pintype "passive"))
      (node (ref "R13") (pin "1") (pinfunction "1_1") (pintype "passive"))
      (node (ref "R15") (pin "1") (pinfunction "1_1") (pintype "passive"))
      (node (ref "R17") (pin "1") (pinfunction "1_1") (pintype "passive"))
      (node (ref "R19") (pin "1") (pinfunction "1_1") (pintype "passive"))
      (node (ref "R3") (pin "1") (pinfunction "1_1") (pintype "passive"))
      (node (ref "R5") (pin "2") (pinfunction "2_2") (pintype "passive"))
      (node (ref "R6") (pin "1") (pinfunction "1_1") (pintype "passive"))
      (node (ref "RTB") (pin "P$1") (pinfunction "A_P$1") (pintype "passive"))
      (node (ref "SOC1") (pin "12") (pinfunction "VSSA/VREF-_12") (pintype "passive"))
      (node (ref "SOC1") (pin "18") (pinfunction "VSS(1)_18") (pintype "passive"))
      (node (ref "SOC1") (pin "31") (pinfunction "VSS(2)_31") (pintype "passive"))
      (node (ref "SOC1") (pin "47") (pinfunction "VSS(3)_47") (pintype "passive"))
      (node (ref "SOC1") (pin "63") (pinfunction "VSS(4)_63") (pintype "passive"))
      (node (ref "SOC2") (pin "1") (pinfunction "GND_1") (pintype "bidirectional"))
      (node (ref "SOC2") (pin "15") (pinfunction "GND_15") (pintype "bidirectional"))
      (node (ref "SOC2") (pin "24") (pinfunction "IO2_24") (pintype "bidirectional"))
      (node (ref "SOC2") (pin "38") (pinfunction "GND_38") (pintype "bidirectional"))
      (node (ref "SOC2") (pin "GND") (pinfunction "GND_GND") (pintype "bidirectional"))
      (node (ref "STM32-BREAKOUT") (pin "2") (pinfunction "2_2") (pintype "passive"))
      (node (ref "STMRESET") (pin "P$1") (pinfunction "A_P$1") (pintype "passive"))
      (node (ref "U$17") (pin "P2") (pinfunction "P2_P2") (pintype "bidirectional"))
      (node (ref "UPB") (pin "P$1") (pinfunction "A_P$1") (pintype "passive"))
      (node (ref "USB") (pin "GND") (pinfunction "GND_GND") (pintype "bidirectional"))
      (node (ref "USB") (pin "P$10") (pinfunction "GND_P$10") (pintype "bidirectional"))
      (node (ref "USB") (pin "P$11") (pinfunction "GND_P$11") (pintype "bidirectional"))
      (node (ref "USB") (pin "P$6") (pinfunction "GND_P$6") (pintype "bidirectional"))
      (node (ref "USB") (pin "P$7") (pinfunction "GND_P$7") (pintype "bidirectional"))
      (node (ref "USB") (pin "P$8") (pinfunction "GND_P$8") (pintype "bidirectional"))
      (node (ref "USB") (pin "P$9") (pinfunction "GND_P$9") (pintype "bidirectional"))
    )
    (net (code "20") (name "GPIO_APA102_DATA") (class "Default")
      (node (ref "APA102-1") (pin "4") (pinfunction "DI_4") (pintype "bidirectional"))
      (node (ref "SOC1") (pin "39") (pinfunction "PC8_39") (pintype "passive"))
      (node (ref "STM32-BREAKOUT") (pin "20") (pinfunction "20_20") (pintype "passive"))
    )
    (net (code "21") (name "GPIO_APA106_DATA") (class "Default")
      (node (ref "APA106-1") (pin "1") (pinfunction "DIN_1") (pintype "input"))
      (node (ref "SOC1") (pin "38") (pinfunction "PC7_38") (pintype "passive"))
      (node (ref "STM32-BREAKOUT") (pin "22") (pinfunction "22_22") (pintype "passive"))
    )
    (net (code "22") (name "IO12") (class "Default")
      (node (ref "ESP-BREAKOUT") (pin "14") (pinfunction "14_14") (pintype "passive"))
      (node (ref "SOC2") (pin "14") (pinfunction "IO12_14") (pintype "bidirectional"))
    )
    (net (code "23") (name "IO13") (class "Default")
      (node (ref "ESP-BREAKOUT") (pin "16") (pinfunction "16_16") (pintype "passive"))
      (node (ref "SOC2") (pin "16") (pinfunction "IO13_16") (pintype "bidirectional"))
    )
    (net (code "24") (name "IO14") (class "Default")
      (node (ref "ESP-BREAKOUT") (pin "13") (pinfunction "13_13") (pintype "passive"))
      (node (ref "SOC2") (pin "13") (pinfunction "IO14_13") (pintype "bidirectional"))
    )
    (net (code "25") (name "IO15") (class "Default")
      (node (ref "ESP-BREAKOUT") (pin "23") (pinfunction "23_23") (pintype "passive"))
      (node (ref "SOC2") (pin "23") (pinfunction "IO15_23") (pintype "bidirectional"))
    )
    (net (code "26") (name "IO16") (class "Default")
      (node (ref "ESP-BREAKOUT") (pin "27") (pinfunction "27_27") (pintype "passive"))
      (node (ref "SOC2") (pin "27") (pinfunction "IO16_27") (pintype "bidirectional"))
    )
    (net (code "27") (name "IO17") (class "Default")
      (node (ref "ESP-BREAKOUT") (pin "28") (pinfunction "28_28") (pintype "passive"))
      (node (ref "SOC2") (pin "28") (pinfunction "IO17_28") (pintype "bidirectional"))
    )
    (net (code "28") (name "IO22") (class "Default")
      (node (ref "ESP-BREAKOUT") (pin "36") (pinfunction "36_36") (pintype "passive"))
      (node (ref "SOC2") (pin "36") (pinfunction "IO22_36") (pintype "bidirectional"))
    )
    (net (code "29") (name "IO23") (class "Default")
      (node (ref "ESP-BREAKOUT") (pin "37") (pinfunction "37_37") (pintype "passive"))
      (node (ref "SOC2") (pin "37") (pinfunction "IO23_37") (pintype "bidirectional"))
    )
    (net (code "30") (name "IO25") (class "Default")
      (node (ref "ESP-BREAKOUT") (pin "10") (pinfunction "10_10") (pintype "passive"))
      (node (ref "SOC2") (pin "10") (pinfunction "IO25_10") (pintype "bidirectional"))
    )
    (net (code "31") (name "IO26") (class "Default")
      (node (ref "ESP-BREAKOUT") (pin "11") (pinfunction "11_11") (pintype "passive"))
      (node (ref "SOC2") (pin "11") (pinfunction "IO26_11") (pintype "bidirectional"))
    )
    (net (code "32") (name "IO27") (class "Default")
      (node (ref "ESP-BREAKOUT") (pin "12") (pinfunction "12_12") (pintype "passive"))
      (node (ref "SOC2") (pin "12") (pinfunction "IO27_12") (pintype "bidirectional"))
    )
    (net (code "33") (name "IO32") (class "Default")
      (node (ref "ESP-BREAKOUT") (pin "8") (pinfunction "8_8") (pintype "passive"))
      (node (ref "SOC2") (pin "8") (pinfunction "IO32_8") (pintype "bidirectional"))
    )
    (net (code "34") (name "IO33") (class "Default")
      (node (ref "ESP-BREAKOUT") (pin "9") (pinfunction "9_9") (pintype "passive"))
      (node (ref "SOC2") (pin "9") (pinfunction "IO33_9") (pintype "bidirectional"))
    )
    (net (code "35") (name "IO34") (class "Default")
      (node (ref "ESP-BREAKOUT") (pin "6") (pinfunction "6_6") (pintype "passive"))
      (node (ref "SOC2") (pin "6") (pinfunction "IO34_6") (pintype "bidirectional"))
    )
    (net (code "36") (name "IO35") (class "Default")
      (node (ref "ESP-BREAKOUT") (pin "7") (pinfunction "7_7") (pintype "passive"))
      (node (ref "SOC2") (pin "7") (pinfunction "IO35_7") (pintype "bidirectional"))
    )
    (net (code "37") (name "LCD_BACKLIGHT") (class "Default")
      (node (ref "LCD1") (pin "LED") (pinfunction "LED_LED") (pintype "bidirectional"))
      (node (ref "SOC1") (pin "28") (pinfunction "PB2_28") (pintype "passive"))
      (node (ref "STM32-BREAKOUT") (pin "34") (pinfunction "34_34") (pintype "passive"))
    )
    (net (code "38") (name "LCD_CS") (class "Default")
      (node (ref "LCD1") (pin "CS") (pinfunction "CS_CS") (pintype "bidirectional"))
      (node (ref "SOC1") (pin "9") (pinfunction "PC1_9") (pintype "passive"))
      (node (ref "STM32-BREAKOUT") (pin "15") (pinfunction "15_15") (pintype "passive"))
    )
    (net (code "39") (name "LCD_DATA_CMD") (class "Default")
      (node (ref "LCD1") (pin "A0") (pinfunction "A0_A0") (pintype "bidirectional"))
      (node (ref "SOC1") (pin "8") (pinfunction "PC0_8") (pintype "passive"))
      (node (ref "STM32-BREAKOUT") (pin "13") (pinfunction "13_13") (pintype "passive"))
    )
    (net (code "40") (name "LCD_RESET") (class "Default")
      (node (ref "LCD1") (pin "RESET") (pinfunction "RESET_RESET") (pintype "bidirectional"))
      (node (ref "SOC1") (pin "25") (pinfunction "PC5_25") (pintype "passive"))
      (node (ref "STM32-BREAKOUT") (pin "40") (pinfunction "40_40") (pintype "passive"))
    )
    (net (code "41") (name "MID_BUTTON") (class "Default")
      (node (ref "C19") (pin "1") (pinfunction "1_1") (pintype "passive"))
      (node (ref "MIDB") (pin "P$2") (pinfunction "C_P$2") (pintype "passive"))
      (node (ref "R7") (pin "2") (pinfunction "2_2") (pintype "passive"))
      (node (ref "SOC1") (pin "2") (pinfunction "PC13_2") (pintype "passive"))
      (node (ref "STM32-BREAKOUT") (pin "3") (pinfunction "3_3") (pintype "passive"))
    )
    (net (code "42") (name "NRST") (class "Default")
      (node (ref "C18") (pin "1") (pinfunction "1_1") (pintype "passive"))
      (node (ref "R8") (pin "2") (pinfunction "2_2") (pintype "passive"))
      (node (ref "SOC1") (pin "7") (pinfunction "NRST_7") (pintype "passive"))
      (node (ref "STM32-BREAKOUT") (pin "11") (pinfunction "11_11") (pintype "passive"))
      (node (ref "STMRESET") (pin "P$2") (pinfunction "C_P$2") (pintype "passive"))
    )
    (net (code "43") (name "Net-(APA102-1-CO)") (class "Default")
      (node (ref "APA102-1") (pin "2") (pinfunction "CO_2") (pintype "bidirectional"))
      (node (ref "APA102-2") (pin "5") (pinfunction "CI_5") (pintype "bidirectional"))
    )
    (net (code "44") (name "Net-(APA102-1-DO)") (class "Default")
      (node (ref "APA102-1") (pin "3") (pinfunction "DO_3") (pintype "bidirectional"))
      (node (ref "APA102-2") (pin "4") (pinfunction "DI_4") (pintype "bidirectional"))
    )
    (net (code "45") (name "Net-(APA102-2-CO)") (class "Default")
      (node (ref "APA102-2") (pin "2") (pinfunction "CO_2") (pintype "bidirectional"))
      (node (ref "APA102-3") (pin "5") (pinfunction "CI_5") (pintype "bidirectional"))
    )
    (net (code "46") (name "Net-(APA102-2-DO)") (class "Default")
      (node (ref "APA102-2") (pin "3") (pinfunction "DO_3") (pintype "bidirectional"))
      (node (ref "APA102-3") (pin "4") (pinfunction "DI_4") (pintype "bidirectional"))
    )
    (net (code "47") (name "Net-(APA102-3-CO)") (class "Default")
      (node (ref "APA102-3") (pin "2") (pinfunction "CO_2") (pintype "bidirectional"))
      (node (ref "APA102-4") (pin "5") (pinfunction "CI_5") (pintype "bidirectional"))
    )
    (net (code "48") (name "Net-(APA102-3-DO)") (class "Default")
      (node (ref "APA102-3") (pin "3") (pinfunction "DO_3") (pintype "bidirectional"))
      (node (ref "APA102-4") (pin "4") (pinfunction "DI_4") (pintype "bidirectional"))
    )
    (net (code "49") (name "Net-(APA106-1-DOUT)") (class "Default")
      (node (ref "APA106-1") (pin "4") (pinfunction "DOUT_4") (pintype "output"))
      (node (ref "APA106-2") (pin "1") (pinfunction "DIN_1") (pintype "input"))
    )
    (net (code "50") (name "Net-(APA106-2-DOUT)") (class "Default")
      (node (ref "APA106-2") (pin "4") (pinfunction "DOUT_4") (pintype "output"))
      (node (ref "APA106-3") (pin "1") (pinfunction "DIN_1") (pintype "input"))
    )
    (net (code "51") (name "Net-(APA106-3-DOUT)") (class "Default")
      (node (ref "APA106-3") (pin "4") (pinfunction "DOUT_4") (pintype "output"))
      (node (ref "APA106-4") (pin "1") (pinfunction "DIN_1") (pintype "input"))
    )
    (net (code "52") (name "Net-(APA106-4-DOUT)") (class "Default")
      (node (ref "APA106-4") (pin "4") (pinfunction "DOUT_4") (pintype "output"))
      (node (ref "APA106-5") (pin "1") (pinfunction "DIN_1") (pintype "input"))
    )
    (net (code "53") (name "Net-(APA106-5-DOUT)") (class "Default")
      (node (ref "APA106-5") (pin "4") (pinfunction "DOUT_4") (pintype "output"))
      (node (ref "APA106-6") (pin "1") (pinfunction "DIN_1") (pintype "input"))
    )
    (net (code "54") (name "Net-(C19-Pad2)") (class "Default")
      (node (ref "C19") (pin "2") (pinfunction "2_2") (pintype "passive"))
      (node (ref "R6") (pin "2") (pinfunction "2_2") (pintype "passive"))
    )
    (net (code "55") (name "Net-(C35-Pad2)") (class "Default")
      (node (ref "C35") (pin "2") (pinfunction "2_2") (pintype "passive"))
      (node (ref "R11") (pin "2") (pinfunction "2_2") (pintype "passive"))
    )
    (net (code "56") (name "Net-(C36-Pad2)") (class "Default")
      (node (ref "C36") (pin "2") (pinfunction "2_2") (pintype "passive"))
      (node (ref "R13") (pin "2") (pinfunction "2_2") (pintype "passive"))
    )
    (net (code "57") (name "Net-(C37-Pad2)") (class "Default")
      (node (ref "C37") (pin "2") (pinfunction "2_2") (pintype "passive"))
      (node (ref "R15") (pin "2") (pinfunction "2_2") (pintype "passive"))
    )
    (net (code "58") (name "Net-(C38-Pad2)") (class "Default")
      (node (ref "C38") (pin "2") (pinfunction "2_2") (pintype "passive"))
      (node (ref "R17") (pin "2") (pinfunction "2_2") (pintype "passive"))
    )
    (net (code "59") (name "Net-(C39-Pad2)") (class "Default")
      (node (ref "C39") (pin "2") (pinfunction "2_2") (pintype "passive"))
      (node (ref "R19") (pin "2") (pinfunction "2_2") (pintype "passive"))
    )
    (net (code "60") (name "Net-(CHARGING_CIRCUT-PROG)") (class "Default")
      (node (ref "CHARGING_CIRCUT") (pin "5") (pinfunction "PROG_5") (pintype "bidirectional"))
      (node (ref "R3") (pin "2") (pinfunction "2_2") (pintype "passive"))
    )
    (net (code "61") (name "Net-(CHARGING_CIRCUT-STAT)") (class "Default")
      (node (ref "CHARGING_CIRCUT") (pin "1") (pinfunction "STAT_1") (pintype "bidirectional"))
      (node (ref "LED1") (pin "C") (pinfunction "C_C") (pintype "output"))
    )
    (net (code "62") (name "Net-(IC3-EN)") (class "Default")
      (node (ref "IC3") (pin "5") (pinfunction "EN_5") (pintype "bidirectional"))
      (node (ref "P1") (pin "C") (pinfunction "C_C") (pintype "bidirectional"))
    )
    (net (code "63") (name "Net-(LED1-PadA)") (class "Default")
      (node (ref "LED1") (pin "A") (pinfunction "A_A") (pintype "input"))
      (node (ref "R2") (pin "1") (pinfunction "1_1") (pintype "passive"))
    )
    (net (code "64") (name "Net-(LED2-C)") (class "Default")
      (node (ref "LED2") (pin "K") (pinfunction "C_K") (pintype "output"))
      (node (ref "R10") (pin "2") (pinfunction "2_2") (pintype "passive"))
    )
    (net (code "65") (name "Net-(SOC1-VCAP_1)") (class "Default")
      (node (ref "C17") (pin "1") (pinfunction "1_1") (pintype "passive"))
      (node (ref "SOC1") (pin "30") (pinfunction "VCAP_1_30") (pintype "passive"))
    )
    (net (code "66") (name "OSC_IN") (class "Default")
      (node (ref "C16") (pin "2") (pinfunction "2_2") (pintype "passive"))
      (node (ref "R9") (pin "2") (pinfunction "2_2") (pintype "passive"))
      (node (ref "SOC1") (pin "5") (pinfunction "PH0-OSC_IN_5") (pintype "passive"))
      (node (ref "Y1") (pin "2") (pinfunction "2_2") (pintype "passive"))
    )
    (net (code "67") (name "OSC_OUT") (class "Default")
      (node (ref "C15") (pin "2") (pinfunction "2_2") (pintype "passive"))
      (node (ref "R9") (pin "1") (pinfunction "1_1") (pintype "passive"))
      (node (ref "SOC1") (pin "6") (pinfunction "PH1-OSC_OUT_6") (pintype "passive"))
      (node (ref "Y1") (pin "1") (pinfunction "1_1") (pintype "passive"))
    )
    (net (code "68") (name "PA0") (class "Default")
      (node (ref "SOC1") (pin "14") (pinfunction "PA0_14") (pintype "passive"))
      (node (ref "STM32-BREAKOUT") (pin "23") (pinfunction "23_23") (pintype "passive"))
    )
    (net (code "69") (name "PA1") (class "Default")
      (node (ref "SOC1") (pin "15") (pinfunction "PA1_15") (pintype "passive"))
      (node (ref "STM32-BREAKOUT") (pin "25") (pinfunction "25_25") (pintype "passive"))
    )
    (net (code "70") (name "PA4") (class "Default")
      (node (ref "SOC1") (pin "20") (pinfunction "PA4_20") (pintype "passive"))
      (node (ref "STM32-BREAKOUT") (pin "31") (pinfunction "31_31") (pintype "passive"))
    )
    (net (code "71") (name "PA5") (class "Default")
      (node (ref "SOC1") (pin "21") (pinfunction "PA5_21") (pintype "passive"))
      (node (ref "STM32-BREAKOUT") (pin "33") (pinfunction "33_33") (pintype "passive"))
    )
    (net (code "72") (name "PA6") (class "Default")
      (node (ref "SOC1") (pin "22") (pinfunction "PA6_22") (pintype "passive"))
      (node (ref "STM32-BREAKOUT") (pin "35") (pinfunction "35_35") (pintype "passive"))
    )
    (net (code "73") (name "PA7") (class "Default")
      (node (ref "SOC1") (pin "23") (pinfunction "PA7_23") (pintype "passive"))
      (node (ref "STM32-BREAKOUT") (pin "37") (pinfunction "37_37") (pintype "passive"))
    )
    (net (code "74") (name "PA8") (class "Default")
      (node (ref "SOC1") (pin "41") (pinfunction "PA8_41") (pintype "passive"))
      (node (ref "STM32-BREAKOUT") (pin "16") (pinfunction "16_16") (pintype "passive"))
    )
    (net (code "75") (name "PA15") (class "Default")
      (node (ref "SOC1") (pin "50") (pinfunction "PA15_50") (pintype "passive"))
      (node (ref "STM32-BREAKOUT") (pin "10") (pinfunction "10_10") (pintype "passive"))
    )
    (net (code "76") (name "PB0") (class "Default")
      (node (ref "SOC1") (pin "26") (pinfunction "PB0_26") (pintype "passive"))
      (node (ref "STM32-BREAKOUT") (pin "38") (pinfunction "38_38") (pintype "passive"))
    )
    (net (code "77") (name "PB1") (class "Default")
      (node (ref "SOC1") (pin "27") (pinfunction "PB1_27") (pintype "passive"))
      (node (ref "STM32-BREAKOUT") (pin "36") (pinfunction "36_36") (pintype "passive"))
    )
    (net (code "78") (name "PB3") (class "Default")
      (node (ref "M10") (pin "2") (pinfunction "2_2") (pintype "passive"))
      (node (ref "SOC1") (pin "55") (pinfunction "PB3_55") (pintype "passive"))
    )
    (net (code "79") (name "PB4") (class "Default")
      (node (ref "M10") (pin "3") (pinfunction "3_3") (pintype "passive"))
      (node (ref "SOC1") (pin "56") (pinfunction "PB4_56") (pintype "passive"))
    )
    (net (code "80") (name "PB5") (class "Default")
      (node (ref "M10") (pin "4") (pinfunction "4_4") (pintype "passive"))
      (node (ref "SOC1") (pin "57") (pinfunction "PB5_57") (pintype "passive"))
    )
    (net (code "81") (name "PB13") (class "Default")
      (node (ref "SOC1") (pin "34") (pinfunction "PB13_34") (pintype "passive"))
      (node (ref "STM32-BREAKOUT") (pin "21") (pinfunction "21_21") (pintype "passive"))
    )
    (net (code "82") (name "PB14") (class "Default")
      (node (ref "SOC1") (pin "35") (pinfunction "PB14_35") (pintype "passive"))
      (node (ref "STM32-BREAKOUT") (pin "28") (pinfunction "28_28") (pintype "passive"))
    )
    (net (code "83") (name "PB15") (class "Default")
      (node (ref "SOC1") (pin "36") (pinfunction "PB15_36") (pintype "passive"))
      (node (ref "STM32-BREAKOUT") (pin "26") (pinfunction "26_26") (pintype "passive"))
    )
    (net (code "84") (name "PC6") (class "Default")
      (node (ref "SOC1") (pin "37") (pinfunction "PC6_37") (pintype "passive"))
      (node (ref "STM32-BREAKOUT") (pin "24") (pinfunction "24_24") (pintype "passive"))
    )
    (net (code "85") (name "SD1") (class "Default")
      (node (ref "ESP-BREAKOUT") (pin "22") (pinfunction "22_22") (pintype "passive"))
      (node (ref "SOC2") (pin "22") (pinfunction "SD1_22") (pintype "bidirectional"))
    )
    (net (code "86") (name "SD2") (class "Default")
      (node (ref "ESP-BREAKOUT") (pin "17") (pinfunction "17_17") (pintype "passive"))
      (node (ref "SOC2") (pin "17") (pinfunction "SD2_17") (pintype "bidirectional"))
    )
    (net (code "87") (name "SD3") (class "Default")
      (node (ref "ESP-BREAKOUT") (pin "18") (pinfunction "18_18") (pintype "passive"))
      (node (ref "SOC2") (pin "18") (pinfunction "SD3_18") (pintype "bidirectional"))
    )
    (net (code "88") (name "SDO") (class "Default")
      (node (ref "ESP-BREAKOUT") (pin "21") (pinfunction "21_21") (pintype "passive"))
      (node (ref "SOC2") (pin "21") (pinfunction "SDO_21") (pintype "bidirectional"))
    )
    (net (code "89") (name "SD_CS") (class "Default")
      (node (ref "LCD1") (pin "SD_CS") (pinfunction "SD_CS_SD_CS") (pintype "bidirectional"))
      (node (ref "SOC1") (pin "24") (pinfunction "PC4_24") (pintype "passive"))
      (node (ref "STM32-BREAKOUT") (pin "39") (pinfunction "39_39") (pintype "passive"))
    )
    (net (code "90") (name "SENSOR_VN") (class "Default")
      (node (ref "ESP-BREAKOUT") (pin "5") (pinfunction "5_5") (pintype "passive"))
      (node (ref "SOC2") (pin "5") (pinfunction "SENSOR_VN_5") (pintype "bidirectional"))
    )
    (net (code "91") (name "SENSOR_VP") (class "Default")
      (node (ref "ESP-BREAKOUT") (pin "4") (pinfunction "4_4") (pintype "passive"))
      (node (ref "SOC2") (pin "4") (pinfunction "SENSOR_VP_4") (pintype "bidirectional"))
    )
    (net (code "92") (name "SIMPLE_LED") (class "Default")
      (node (ref "R10") (pin "1") (pinfunction "1_1") (pintype "passive"))
      (node (ref "SOC1") (pin "51") (pinfunction "PC10_51") (pintype "passive"))
      (node (ref "STM32-BREAKOUT") (pin "8") (pinfunction "8_8") (pintype "passive"))
    )
    (net (code "93") (name "SPI2_LCD_MOSI") (class "Default")
      (node (ref "LCD1") (pin "SDA") (pinfunction "SDA_SDA") (pintype "bidirectional"))
      (node (ref "SOC1") (pin "11") (pinfunction "PC3_11") (pintype "passive"))
      (node (ref "STM32-BREAKOUT") (pin "19") (pinfunction "19_19") (pintype "passive"))
    )
    (net (code "94") (name "SPI2_LCD_SCK") (class "Default")
      (node (ref "LCD1") (pin "SCK") (pinfunction "SCK_SCK") (pintype "bidirectional"))
      (node (ref "SOC1") (pin "29") (pinfunction "PB10_29") (pintype "passive"))
      (node (ref "STM32-BREAKOUT") (pin "32") (pinfunction "32_32") (pintype "passive"))
    )
    (net (code "95") (name "SPI3_SD_MISO") (class "Default")
      (node (ref "LCD1") (pin "SD_MISO") (pinfunction "SD_MISO_SD_MISO") (pintype "bidirectional"))
      (node (ref "SOC1") (pin "52") (pinfunction "PC11_52") (pintype "passive"))
      (node (ref "STM32-BREAKOUT") (pin "6") (pinfunction "6_6") (pintype "passive"))
    )
    (net (code "96") (name "SPI3_SD_MOSI") (class "Default")
      (node (ref "LCD1") (pin "SD_MOSI") (pinfunction "SD_MOSI_SD_MOSI") (pintype "bidirectional"))
      (node (ref "SOC1") (pin "53") (pinfunction "PC12_53") (pintype "passive"))
      (node (ref "STM32-BREAKOUT") (pin "4") (pinfunction "4_4") (pintype "passive"))
    )
    (net (code "97") (name "SPI3_SD_SCK") (class "Default")
      (node (ref "LCD1") (pin "SD_SCK") (pinfunction "SD_SCK_SD_SCK") (pintype "bidirectional"))
      (node (ref "SOC1") (pin "33") (pinfunction "PB12_33") (pintype "passive"))
      (node (ref "STM32-BREAKOUT") (pin "30") (pinfunction "30_30") (pintype "passive"))
    )
    (net (code "98") (name "SYS_JTCK_SWCLK") (class "Default")
      (node (ref "LINK1") (pin "SWDCLK") (pinfunction "SWDCLK_SWDCLK") (pintype "input"))
      (node (ref "SOC1") (pin "49") (pinfunction "PA14_49") (pintype "passive"))
    )
    (net (code "99") (name "SYS_JTMS_SWDIO") (class "Default")
      (node (ref "LINK1") (pin "SWDIO") (pinfunction "SWDIO_SWDIO") (pintype "bidirectional"))
      (node (ref "SOC1") (pin "46") (pinfunction "PA13_46") (pintype "passive"))
    )
    (net (code "100") (name "TIM_APA102_CLK") (class "Default")
      (node (ref "APA102-1") (pin "5") (pinfunction "CI_5") (pintype "bidirectional"))
      (node (ref "SOC1") (pin "40") (pinfunction "PC9_40") (pintype "passive"))
      (node (ref "STM32-BREAKOUT") (pin "18") (pinfunction "18_18") (pintype "passive"))
    )
    (net (code "101") (name "USART1_RX_TO_ESP_TX_PIN_4") (class "Default")
      (node (ref "R22") (pin "2") (pinfunction "2_2") (pintype "passive"))
      (node (ref "SOC1") (pin "43") (pinfunction "PA10_43") (pintype "passive"))
      (node (ref "STM32-BREAKOUT") (pin "12") (pinfunction "12_12") (pintype "passive"))
    )
    (net (code "102") (name "USART1_TX_TO_ESP_RX_PIN_5") (class "Default")
      (node (ref "R21") (pin "2") (pinfunction "2_2") (pintype "passive"))
      (node (ref "SOC1") (pin "42") (pinfunction "PA9_42") (pintype "passive"))
      (node (ref "STM32-BREAKOUT") (pin "14") (pinfunction "14_14") (pintype "passive"))
    )
    (net (code "103") (name "USART2_RX") (class "Default")
      (node (ref "SOC1") (pin "17") (pinfunction "PA3_17") (pintype "passive"))
      (node (ref "STM32-BREAKOUT") (pin "29") (pinfunction "29_29") (pintype "passive"))
    )
    (net (code "104") (name "USART2_TX") (class "Default")
      (node (ref "SOC1") (pin "16") (pinfunction "PA2_16") (pintype "passive"))
      (node (ref "STM32-BREAKOUT") (pin "27") (pinfunction "27_27") (pintype "passive"))
    )
    (net (code "105") (name "USB_DM") (class "Default")
      (node (ref "SOC1") (pin "44") (pinfunction "PA11_44") (pintype "passive"))
      (node (ref "U$17") (pin "P6") (pinfunction "P6_P6") (pintype "bidirectional"))
      (node (ref "USB") (pin "D+") (pinfunction "D+_D+") (pintype "bidirectional"))
    )
    (net (code "106") (name "USB_DP") (class "Default")
      (node (ref "SOC1") (pin "45") (pinfunction "PA12_45") (pintype "passive"))
      (node (ref "U$17") (pin "P1") (pinfunction "P1_P1") (pintype "bidirectional"))
      (node (ref "USB") (pin "D-") (pinfunction "D-_D-") (pintype "bidirectional"))
    )
    (net (code "107") (name "VCC") (class "Default")
      (node (ref "C10") (pin "1") (pinfunction "1_1") (pintype "passive"))
      (node (ref "C13") (pin "1") (pinfunction "1_1") (pintype "passive"))
      (node (ref "C4") (pin "1") (pinfunction "1_1") (pintype "passive"))
      (node (ref "C5") (pin "1") (pinfunction "1_1") (pintype "passive"))
      (node (ref "C6") (pin "1") (pinfunction "1_1") (pintype "passive"))
      (node (ref "C7") (pin "1") (pinfunction "1_1") (pintype "passive"))
      (node (ref "C8") (pin "1") (pinfunction "1_1") (pintype "passive"))
      (node (ref "C9") (pin "1") (pinfunction "1_1") (pintype "passive"))
      (node (ref "ESP-BREAKOUT") (pin "2") (pinfunction "2_2") (pintype "passive"))
      (node (ref "FB1") (pin "1") (pinfunction "1_1") (pintype "passive"))
      (node (ref "IC3") (pin "1") (pinfunction "VOUT_1") (pintype "bidirectional"))
      (node (ref "LCD1") (pin "VCC") (pinfunction "VCC_VCC") (pintype "bidirectional"))
      (node (ref "M10") (pin "10") (pinfunction "10_10") (pintype "passive"))
      (node (ref "OLED1") (pin "2") (pinfunction "VCC_2") (pintype "power_in"))
      (node (ref "R1") (pin "2") (pinfunction "2_2") (pintype "passive"))
      (node (ref "R12") (pin "1") (pinfunction "1_1") (pintype "passive"))
      (node (ref "R14") (pin "1") (pinfunction "1_1") (pintype "passive"))
      (node (ref "R16") (pin "1") (pinfunction "1_1") (pintype "passive"))
      (node (ref "R18") (pin "1") (pinfunction "1_1") (pintype "passive"))
      (node (ref "R20") (pin "1") (pinfunction "1_1") (pintype "passive"))
      (node (ref "R4") (pin "2") (pinfunction "2_2") (pintype "passive"))
      (node (ref "R7") (pin "1") (pinfunction "1_1") (pintype "passive"))
      (node (ref "R8") (pin "1") (pinfunction "1_1") (pintype "passive"))
      (node (ref "SOC1") (pin "1") (pinfunction "VBAT_1") (pintype "passive"))
      (node (ref "SOC1") (pin "19") (pinfunction "VDD(1)_19") (pintype "passive"))
      (node (ref "SOC1") (pin "32") (pinfunction "VDD(2)_32") (pintype "passive"))
      (node (ref "SOC1") (pin "48") (pinfunction "VDD(3)_48") (pintype "passive"))
      (node (ref "SOC1") (pin "64") (pinfunction "VDD(4)_64") (pintype "passive"))
      (node (ref "SOC2") (pin "2") (pinfunction "3V3_2") (pintype "bidirectional"))
      (node (ref "STM32-BREAKOUT") (pin "1") (pinfunction "1_1") (pintype "passive"))
    )
    (net (code "108") (name "VCC0") (class "Default")
      (node (ref "C2") (pin "1") (pinfunction "1_1") (pintype "passive"))
      (node (ref "CHARGING_CIRCUT") (pin "4") (pinfunction "VDD_4") (pintype "bidirectional"))
      (node (ref "R2") (pin "2") (pinfunction "2_2") (pintype "passive"))
      (node (ref "USB") (pin "+5V") (pinfunction "+5V_+5V") (pintype "bidirectional"))
    )
    (net (code "109") (name "VCC1") (class "Default")
      (node (ref "C1") (pin "1") (pinfunction "1_1") (pintype "passive"))
      (node (ref "CHARGING_CIRCUT") (pin "3") (pinfunction "VBAT_3") (pintype "bidirectional"))
      (node (ref "CN1") (pin "1") (pinfunction "2_1") (pintype "passive"))
      (node (ref "RESETTABLE-FUSE") (pin "1") (pinfunction "1_1") (pintype "bidirectional"))
    )
    (net (code "110") (name "VDDA") (class "Default")
      (node (ref "C11") (pin "1") (pinfunction "1_1") (pintype "passive"))
      (node (ref "C12") (pin "1") (pinfunction "1_1") (pintype "passive"))
      (node (ref "FB1") (pin "2") (pinfunction "2_2") (pintype "passive"))
      (node (ref "SOC1") (pin "13") (pinfunction "VDDA/VREF+_13") (pintype "passive"))
    )
    (net (code "111") (name "VIN") (class "Default")
      (node (ref "APA102-1") (pin "1") (pinfunction "VCC_1") (pintype "bidirectional"))
      (node (ref "APA102-2") (pin "1") (pinfunction "VCC_1") (pintype "bidirectional"))
      (node (ref "APA102-3") (pin "1") (pinfunction "VCC_1") (pintype "bidirectional"))
      (node (ref "APA102-4") (pin "1") (pinfunction "VCC_1") (pintype "bidirectional"))
      (node (ref "APA106-1") (pin "2") (pinfunction "VDD_2") (pintype "bidirectional"))
      (node (ref "APA106-2") (pin "2") (pinfunction "VDD_2") (pintype "bidirectional"))
      (node (ref "APA106-3") (pin "2") (pinfunction "VDD_2") (pintype "bidirectional"))
      (node (ref "APA106-4") (pin "2") (pinfunction "VDD_2") (pintype "bidirectional"))
      (node (ref "APA106-5") (pin "2") (pinfunction "VDD_2") (pintype "bidirectional"))
      (node (ref "APA106-6") (pin "2") (pinfunction "VDD_2") (pintype "bidirectional"))
      (node (ref "C14") (pin "1") (pinfunction "1_1") (pintype "passive"))
      (node (ref "C20") (pin "1") (pinfunction "1_1") (pintype "passive"))
      (node (ref "C21") (pin "1") (pinfunction "1_1") (pintype "passive"))
      (node (ref "C22") (pin "1") (pinfunction "1_1") (pintype "passive"))
      (node (ref "C23") (pin "1") (pinfunction "1_1") (pintype "passive"))
      (node (ref "C24") (pin "1") (pinfunction "1_1") (pintype "passive"))
      (node (ref "C25") (pin "1") (pinfunction "1_1") (pintype "passive"))
      (node (ref "C26") (pin "1") (pinfunction "1_1") (pintype "passive"))
      (node (ref "C27") (pin "1") (pinfunction "1_1") (pintype "passive"))
      (node (ref "C3") (pin "2") (pinfunction "2_2") (pintype "passive"))
      (node (ref "C31") (pin "1") (pinfunction "1_1") (pintype "passive"))
      (node (ref "ESP32PH") (pin "VCC") (pinfunction "VCC_VCC") (pintype "power_in"))
      (node (ref "IC3") (pin "4") (pinfunction "VIN_4") (pintype "bidirectional"))
      (node (ref "LINK1") (pin "VCC") (pinfunction "VCC_VCC") (pintype "power_in"))
      (node (ref "P1") (pin "2") (pinfunction "2_2") (pintype "bidirectional"))
      (node (ref "RESETTABLE-FUSE") (pin "2") (pinfunction "2_2") (pintype "bidirectional"))
    )
    (net (code "112") (name "unconnected-(APA102-4-CO-Pad2)") (class "Default")
      (node (ref "APA102-4") (pin "2") (pinfunction "CO_2") (pintype "bidirectional"))
    )
    (net (code "113") (name "unconnected-(APA102-4-DO-Pad3)") (class "Default")
      (node (ref "APA102-4") (pin "3") (pinfunction "DO_3") (pintype "bidirectional"))
    )
    (net (code "114") (name "unconnected-(APA106-1-GND-Pad3)") (class "Default")
      (node (ref "APA106-1") (pin "3") (pinfunction "GND_3") (pintype "bidirectional"))
    )
    (net (code "115") (name "unconnected-(APA106-2-GND-Pad3)") (class "Default")
      (node (ref "APA106-2") (pin "3") (pinfunction "GND_3") (pintype "bidirectional"))
    )
    (net (code "116") (name "unconnected-(APA106-3-GND-Pad3)") (class "Default")
      (node (ref "APA106-3") (pin "3") (pinfunction "GND_3") (pintype "bidirectional"))
    )
    (net (code "117") (name "unconnected-(APA106-4-GND-Pad3)") (class "Default")
      (node (ref "APA106-4") (pin "3") (pinfunction "GND_3") (pintype "bidirectional"))
    )
    (net (code "118") (name "unconnected-(APA106-5-GND-Pad3)") (class "Default")
      (node (ref "APA106-5") (pin "3") (pinfunction "GND_3") (pintype "bidirectional"))
    )
    (net (code "119") (name "unconnected-(APA106-6-DOUT-Pad4)") (class "Default")
      (node (ref "APA106-6") (pin "4") (pinfunction "DOUT_4") (pintype "output"))
    )
    (net (code "120") (name "unconnected-(APA106-6-GND-Pad3)") (class "Default")
      (node (ref "APA106-6") (pin "3") (pinfunction "GND_3") (pintype "bidirectional"))
    )
    (net (code "121") (name "unconnected-(ESP-BREAKOUT-Pad3)") (class "Default")
      (node (ref "ESP-BREAKOUT") (pin "3") (pinfunction "3_3") (pintype "passive"))
    )
    (net (code "122") (name "unconnected-(ESP-BREAKOUT-Pad32)") (class "Default")
      (node (ref "ESP-BREAKOUT") (pin "32") (pinfunction "32_32") (pintype "passive"))
    )
    (net (code "123") (name "unconnected-(ESP-BREAKOUT-Pad39)") (class "Default")
      (node (ref "ESP-BREAKOUT") (pin "39") (pinfunction "39_39") (pintype "passive"))
    )
    (net (code "124") (name "unconnected-(ESP-BREAKOUT-Pad40)") (class "Default")
      (node (ref "ESP-BREAKOUT") (pin "40") (pinfunction "40_40") (pintype "passive"))
    )
    (net (code "125") (name "unconnected-(IC3-ADJ-Pad8)") (class "Default")
      (node (ref "IC3") (pin "8") (pinfunction "ADJ_8") (pintype "bidirectional"))
    )
    (net (code "126") (name "unconnected-(SOC2-NC-Pad32)") (class "Default")
      (node (ref "SOC2") (pin "32") (pinfunction "NC_32") (pintype "bidirectional"))
    )
    (net (code "127") (name "unconnected-(U$17-PadP3)") (class "Default")
      (node (ref "U$17") (pin "P3") (pinfunction "P3_P3") (pintype "bidirectional"))
    )
    (net (code "128") (name "unconnected-(U$17-PadP4)") (class "Default")
      (node (ref "U$17") (pin "P4") (pinfunction "P4_P4") (pintype "bidirectional"))
    )
    (net (code "129") (name "unconnected-(U$17-PadP5)") (class "Default")
      (node (ref "U$17") (pin "P5") (pinfunction "P5_P5") (pintype "bidirectional"))
    )
    (net (code "130") (name "unconnected-(USB-PadID)") (class "Default")
      (node (ref "USB") (pin "ID") (pinfunction "ID_ID") (pintype "bidirectional"))
    )
  )
)
